# protol.net
KiCad netlist of a schematic drawn in EAGLE
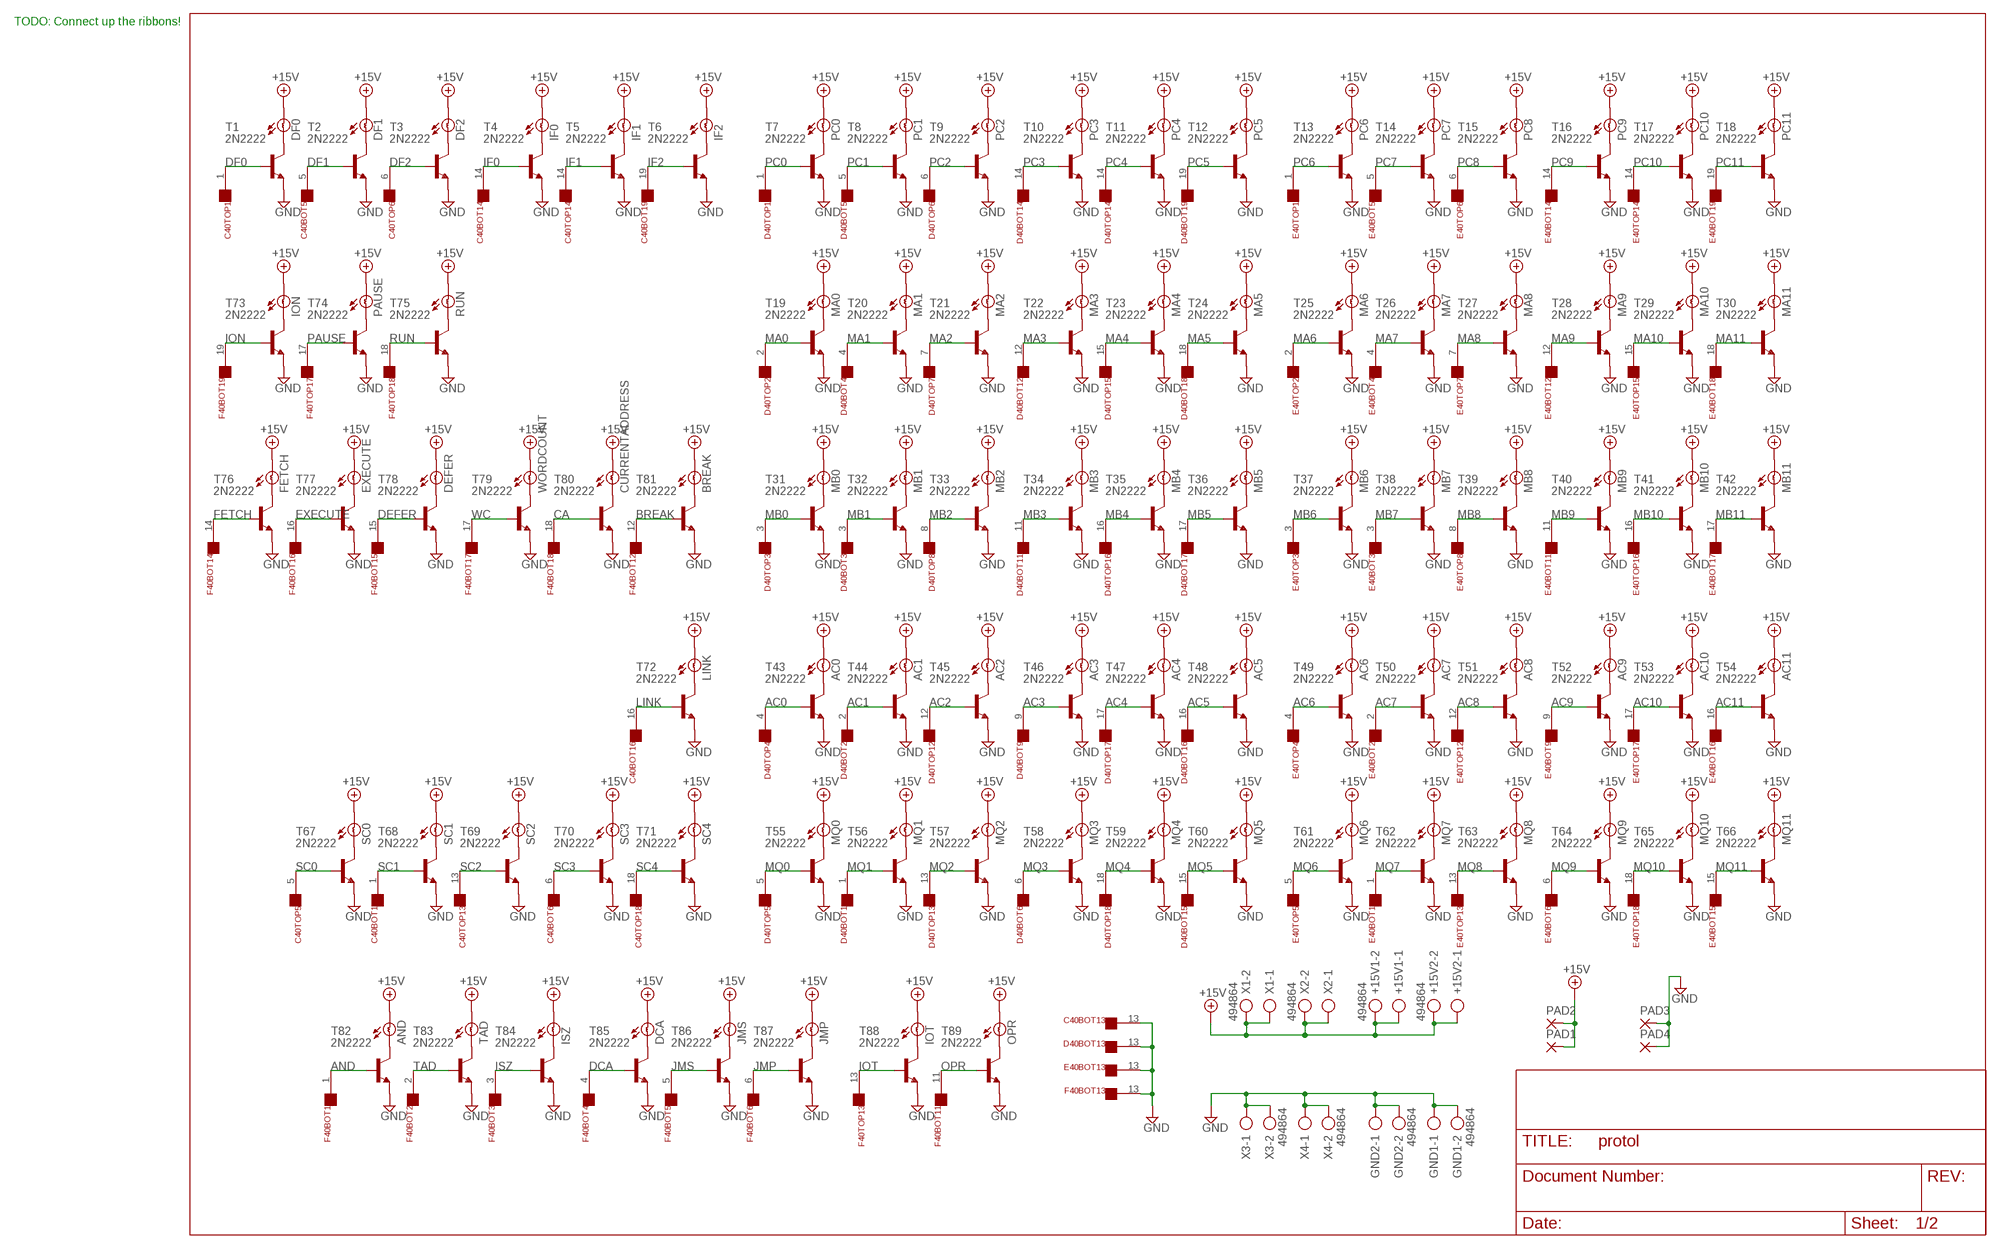
[diagram p0: schematic, sheet 1]
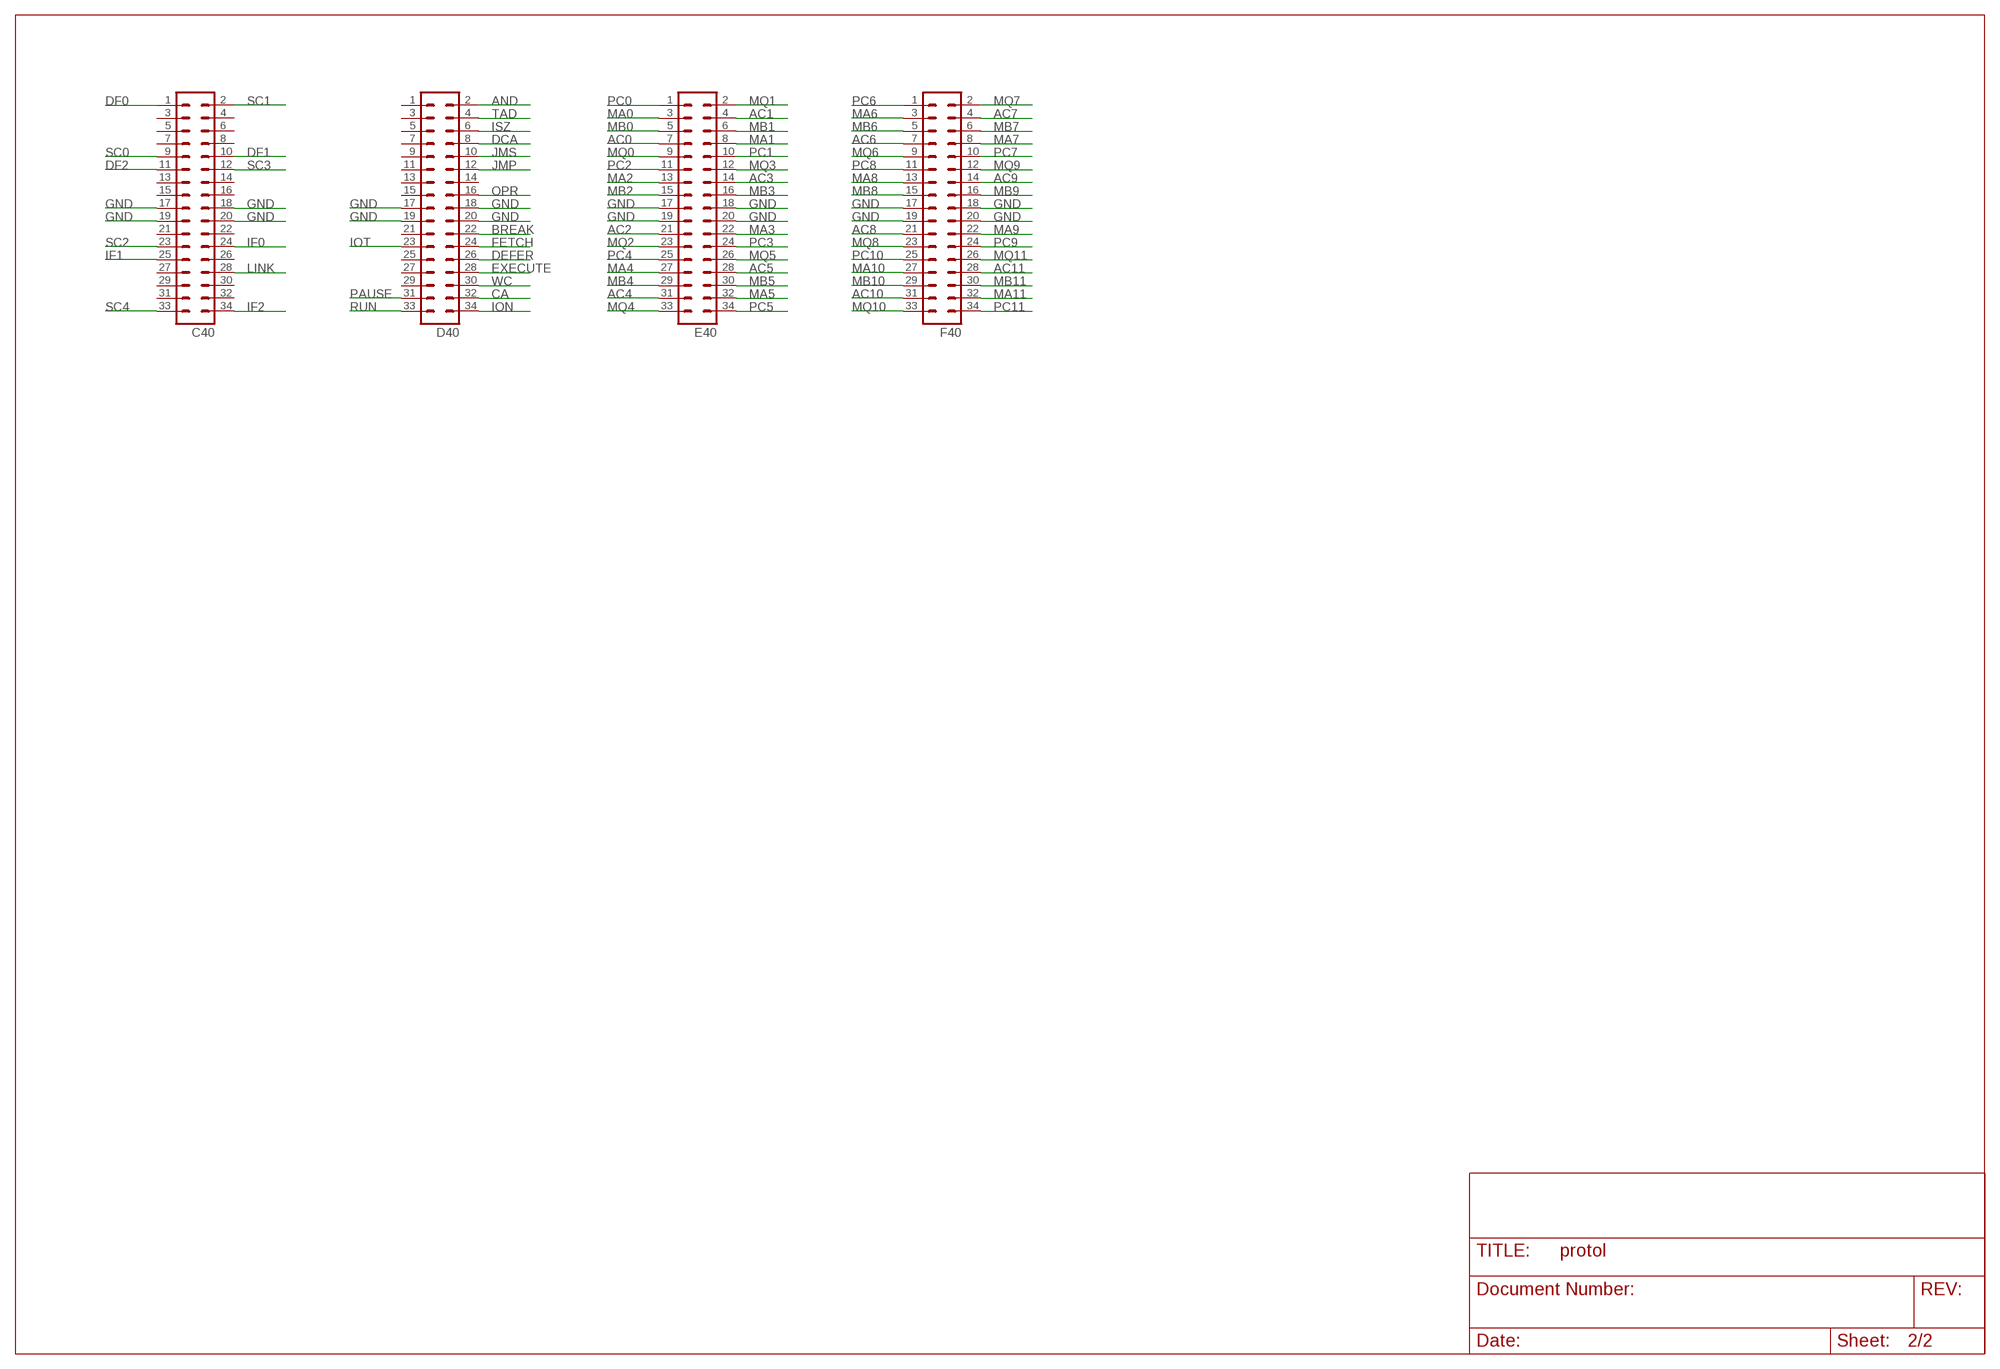
[diagram p1: schematic, sheet 2]

(export (version "E")
  (design (tool "Eeschema 10.0.6"))
  (components
    (comp (ref "C40")
      (value "MA17-2")
      (footprint "eagle-import:MA17-2")
      (libsource (lib "eagle-import") (part "MA17-2"))
    )
    (comp (ref "D40")
      (value "MA17-2")
      (footprint "eagle-import:MA17-2")
      (libsource (lib "eagle-import") (part "MA17-2"))
    )
    (comp (ref "E40")
      (value "MA17-2")
      (footprint "eagle-import:MA17-2")
      (libsource (lib "eagle-import") (part "MA17-2"))
    )
    (comp (ref "F40")
      (value "MA17-2")
      (footprint "eagle-import:MA17-2")
      (libsource (lib "eagle-import") (part "MA17-2"))
    )
    (comp (ref "+15V1")
      (value "494864")
      (footprint "eagle-import:AK500_2")
      (libsource (lib "eagle-import") (part "AK500/2"))
    )
    (comp (ref "+15V2")
      (value "494864")
      (footprint "eagle-import:AK500_2")
      (libsource (lib "eagle-import") (part "AK500/2"))
    )
    (comp (ref "AC0")
      (value "BULB")
      (footprint "eagle-import:BULB")
      (libsource (lib "eagle-import") (part "BULB"))
    )
    (comp (ref "AC1")
      (value "BULB")
      (footprint "eagle-import:BULB")
      (libsource (lib "eagle-import") (part "BULB"))
    )
    (comp (ref "AC2")
      (value "BULB")
      (footprint "eagle-import:BULB")
      (libsource (lib "eagle-import") (part "BULB"))
    )
    (comp (ref "AC3")
      (value "BULB")
      (footprint "eagle-import:BULB")
      (libsource (lib "eagle-import") (part "BULB"))
    )
    (comp (ref "AC4")
      (value "BULB")
      (footprint "eagle-import:BULB")
      (libsource (lib "eagle-import") (part "BULB"))
    )
    (comp (ref "AC5")
      (value "BULB")
      (footprint "eagle-import:BULB")
      (libsource (lib "eagle-import") (part "BULB"))
    )
    (comp (ref "AC6")
      (value "BULB")
      (footprint "eagle-import:BULB")
      (libsource (lib "eagle-import") (part "BULB"))
    )
    (comp (ref "AC7")
      (value "BULB")
      (footprint "eagle-import:BULB")
      (libsource (lib "eagle-import") (part "BULB"))
    )
    (comp (ref "AC8")
      (value "BULB")
      (footprint "eagle-import:BULB")
      (libsource (lib "eagle-import") (part "BULB"))
    )
    (comp (ref "AC9")
      (value "BULB")
      (footprint "eagle-import:BULB")
      (libsource (lib "eagle-import") (part "BULB"))
    )
    (comp (ref "AC10")
      (value "BULB")
      (footprint "eagle-import:BULB")
      (libsource (lib "eagle-import") (part "BULB"))
    )
    (comp (ref "AC11")
      (value "BULB")
      (footprint "eagle-import:BULB")
      (libsource (lib "eagle-import") (part "BULB"))
    )
    (comp (ref "AND")
      (value "BULB")
      (footprint "eagle-import:BULB")
      (libsource (lib "eagle-import") (part "BULB"))
    )
    (comp (ref "BREAK")
      (value "BULB")
      (footprint "eagle-import:BULB")
      (libsource (lib "eagle-import") (part "BULB"))
    )
    (comp (ref "C40BOT")
      (value "FLEX19")
      (footprint "eagle-import:FLEX19")
      (libsource (lib "eagle-import") (part "FLEX19"))
    )
    (comp (ref "C40TOP")
      (value "FLEX19")
      (footprint "eagle-import:FLEX19")
      (libsource (lib "eagle-import") (part "FLEX19"))
    )
    (comp (ref "CURRENTADDRESS")
      (value "BULB")
      (footprint "eagle-import:BULB")
      (libsource (lib "eagle-import") (part "BULB"))
    )
    (comp (ref "D40BOT")
      (value "FLEX19")
      (footprint "eagle-import:FLEX19")
      (libsource (lib "eagle-import") (part "FLEX19"))
    )
    (comp (ref "D40TOP")
      (value "FLEX19")
      (footprint "eagle-import:FLEX19")
      (libsource (lib "eagle-import") (part "FLEX19"))
    )
    (comp (ref "DCA")
      (value "BULB")
      (footprint "eagle-import:BULB")
      (libsource (lib "eagle-import") (part "BULB"))
    )
    (comp (ref "DEFER")
      (value "BULB")
      (footprint "eagle-import:BULB")
      (libsource (lib "eagle-import") (part "BULB"))
    )
    (comp (ref "DF0")
      (value "BULB")
      (footprint "eagle-import:BULB")
      (libsource (lib "eagle-import") (part "BULB"))
    )
    (comp (ref "DF1")
      (value "BULB")
      (footprint "eagle-import:BULB")
      (libsource (lib "eagle-import") (part "BULB"))
    )
    (comp (ref "DF2")
      (value "BULB")
      (footprint "eagle-import:BULB")
      (libsource (lib "eagle-import") (part "BULB"))
    )
    (comp (ref "E40BOT")
      (value "FLEX19")
      (footprint "eagle-import:FLEX19")
      (libsource (lib "eagle-import") (part "FLEX19"))
    )
    (comp (ref "E40TOP")
      (value "FLEX19")
      (footprint "eagle-import:FLEX19")
      (libsource (lib "eagle-import") (part "FLEX19"))
    )
    (comp (ref "EXECUTE")
      (value "BULB")
      (footprint "eagle-import:BULB")
      (libsource (lib "eagle-import") (part "BULB"))
    )
    (comp (ref "F40BOT")
      (value "FLEX19")
      (footprint "eagle-import:FLEX19")
      (libsource (lib "eagle-import") (part "FLEX19"))
    )
    (comp (ref "F40TOP")
      (value "FLEX19")
      (footprint "eagle-import:FLEX19")
      (libsource (lib "eagle-import") (part "FLEX19"))
    )
    (comp (ref "FETCH")
      (value "BULB")
      (footprint "eagle-import:BULB")
      (libsource (lib "eagle-import") (part "BULB"))
    )
    (comp (ref "GND1")
      (value "494864")
      (footprint "eagle-import:AK500_2")
      (libsource (lib "eagle-import") (part "AK500/2"))
    )
    (comp (ref "GND2")
      (value "494864")
      (footprint "eagle-import:AK500_2")
      (libsource (lib "eagle-import") (part "AK500/2"))
    )
    (comp (ref "IF0")
      (value "BULB")
      (footprint "eagle-import:BULB")
      (libsource (lib "eagle-import") (part "BULB"))
    )
    (comp (ref "IF1")
      (value "BULB")
      (footprint "eagle-import:BULB")
      (libsource (lib "eagle-import") (part "BULB"))
    )
    (comp (ref "IF2")
      (value "BULB")
      (footprint "eagle-import:BULB")
      (libsource (lib "eagle-import") (part "BULB"))
    )
    (comp (ref "ION")
      (value "BULB")
      (footprint "eagle-import:BULB")
      (libsource (lib "eagle-import") (part "BULB"))
    )
    (comp (ref "IOT")
      (value "BULB")
      (footprint "eagle-import:BULB")
      (libsource (lib "eagle-import") (part "BULB"))
    )
    (comp (ref "ISZ")
      (value "BULB")
      (footprint "eagle-import:BULB")
      (libsource (lib "eagle-import") (part "BULB"))
    )
    (comp (ref "JMP")
      (value "BULB")
      (footprint "eagle-import:BULB")
      (libsource (lib "eagle-import") (part "BULB"))
    )
    (comp (ref "JMS")
      (value "BULB")
      (footprint "eagle-import:BULB")
      (libsource (lib "eagle-import") (part "BULB"))
    )
    (comp (ref "LINK")
      (value "BULB")
      (footprint "eagle-import:BULB")
      (libsource (lib "eagle-import") (part "BULB"))
    )
    (comp (ref "MA0")
      (value "BULB")
      (footprint "eagle-import:BULB")
      (libsource (lib "eagle-import") (part "BULB"))
    )
    (comp (ref "MA1")
      (value "BULB")
      (footprint "eagle-import:BULB")
      (libsource (lib "eagle-import") (part "BULB"))
    )
    (comp (ref "MA2")
      (value "BULB")
      (footprint "eagle-import:BULB")
      (libsource (lib "eagle-import") (part "BULB"))
    )
    (comp (ref "MA3")
      (value "BULB")
      (footprint "eagle-import:BULB")
      (libsource (lib "eagle-import") (part "BULB"))
    )
    (comp (ref "MA4")
      (value "BULB")
      (footprint "eagle-import:BULB")
      (libsource (lib "eagle-import") (part "BULB"))
    )
    (comp (ref "MA5")
      (value "BULB")
      (footprint "eagle-import:BULB")
      (libsource (lib "eagle-import") (part "BULB"))
    )
    (comp (ref "MA6")
      (value "BULB")
      (footprint "eagle-import:BULB")
      (libsource (lib "eagle-import") (part "BULB"))
    )
    (comp (ref "MA7")
      (value "BULB")
      (footprint "eagle-import:BULB")
      (libsource (lib "eagle-import") (part "BULB"))
    )
    (comp (ref "MA8")
      (value "BULB")
      (footprint "eagle-import:BULB")
      (libsource (lib "eagle-import") (part "BULB"))
    )
    (comp (ref "MA9")
      (value "BULB")
      (footprint "eagle-import:BULB")
      (libsource (lib "eagle-import") (part "BULB"))
    )
    (comp (ref "MA10")
      (value "BULB")
      (footprint "eagle-import:BULB")
      (libsource (lib "eagle-import") (part "BULB"))
    )
    (comp (ref "MA11")
      (value "BULB")
      (footprint "eagle-import:BULB")
      (libsource (lib "eagle-import") (part "BULB"))
    )
    (comp (ref "MB0")
      (value "BULB")
      (footprint "eagle-import:BULB")
      (libsource (lib "eagle-import") (part "BULB"))
    )
    (comp (ref "MB1")
      (value "BULB")
      (footprint "eagle-import:BULB")
      (libsource (lib "eagle-import") (part "BULB"))
    )
    (comp (ref "MB2")
      (value "BULB")
      (footprint "eagle-import:BULB")
      (libsource (lib "eagle-import") (part "BULB"))
    )
    (comp (ref "MB3")
      (value "BULB")
      (footprint "eagle-import:BULB")
      (libsource (lib "eagle-import") (part "BULB"))
    )
    (comp (ref "MB4")
      (value "BULB")
      (footprint "eagle-import:BULB")
      (libsource (lib "eagle-import") (part "BULB"))
    )
    (comp (ref "MB5")
      (value "BULB")
      (footprint "eagle-import:BULB")
      (libsource (lib "eagle-import") (part "BULB"))
    )
    (comp (ref "MB6")
      (value "BULB")
      (footprint "eagle-import:BULB")
      (libsource (lib "eagle-import") (part "BULB"))
    )
    (comp (ref "MB7")
      (value "BULB")
      (footprint "eagle-import:BULB")
      (libsource (lib "eagle-import") (part "BULB"))
    )
    (comp (ref "MB8")
      (value "BULB")
      (footprint "eagle-import:BULB")
      (libsource (lib "eagle-import") (part "BULB"))
    )
    (comp (ref "MB9")
      (value "BULB")
      (footprint "eagle-import:BULB")
      (libsource (lib "eagle-import") (part "BULB"))
    )
    (comp (ref "MB10")
      (value "BULB")
      (footprint "eagle-import:BULB")
      (libsource (lib "eagle-import") (part "BULB"))
    )
    (comp (ref "MB11")
      (value "BULB")
      (footprint "eagle-import:BULB")
      (libsource (lib "eagle-import") (part "BULB"))
    )
    (comp (ref "MQ0")
      (value "BULB")
      (footprint "eagle-import:BULB")
      (libsource (lib "eagle-import") (part "BULB"))
    )
    (comp (ref "MQ1")
      (value "BULB")
      (footprint "eagle-import:BULB")
      (libsource (lib "eagle-import") (part "BULB"))
    )
    (comp (ref "MQ2")
      (value "BULB")
      (footprint "eagle-import:BULB")
      (libsource (lib "eagle-import") (part "BULB"))
    )
    (comp (ref "MQ3")
      (value "BULB")
      (footprint "eagle-import:BULB")
      (libsource (lib "eagle-import") (part "BULB"))
    )
    (comp (ref "MQ4")
      (value "BULB")
      (footprint "eagle-import:BULB")
      (libsource (lib "eagle-import") (part "BULB"))
    )
    (comp (ref "MQ5")
      (value "BULB")
      (footprint "eagle-import:BULB")
      (libsource (lib "eagle-import") (part "BULB"))
    )
    (comp (ref "MQ6")
      (value "BULB")
      (footprint "eagle-import:BULB")
      (libsource (lib "eagle-import") (part "BULB"))
    )
    (comp (ref "MQ7")
      (value "BULB")
      (footprint "eagle-import:BULB")
      (libsource (lib "eagle-import") (part "BULB"))
    )
    (comp (ref "MQ8")
      (value "BULB")
      (footprint "eagle-import:BULB")
      (libsource (lib "eagle-import") (part "BULB"))
    )
    (comp (ref "MQ9")
      (value "BULB")
      (footprint "eagle-import:BULB")
      (libsource (lib "eagle-import") (part "BULB"))
    )
    (comp (ref "MQ10")
      (value "BULB")
      (footprint "eagle-import:BULB")
      (libsource (lib "eagle-import") (part "BULB"))
    )
    (comp (ref "MQ11")
      (value "BULB")
      (footprint "eagle-import:BULB")
      (libsource (lib "eagle-import") (part "BULB"))
    )
    (comp (ref "OPR")
      (value "BULB")
      (footprint "eagle-import:BULB")
      (libsource (lib "eagle-import") (part "BULB"))
    )
    (comp (ref "PAD1")
      (value "2,54/0,8")
      (footprint "eagle-import:2,54_0,8")
      (libsource (lib "eagle-import") (part "2,54/0,8"))
    )
    (comp (ref "PAD2")
      (value "2,54/0,8")
      (footprint "eagle-import:2,54_0,8")
      (libsource (lib "eagle-import") (part "2,54/0,8"))
    )
    (comp (ref "PAD3")
      (value "2,54/0,8")
      (footprint "eagle-import:2,54_0,8")
      (libsource (lib "eagle-import") (part "2,54/0,8"))
    )
    (comp (ref "PAD4")
      (value "2,54/0,8")
      (footprint "eagle-import:2,54_0,8")
      (libsource (lib "eagle-import") (part "2,54/0,8"))
    )
    (comp (ref "PAUSE")
      (value "BULB")
      (footprint "eagle-import:BULB")
      (libsource (lib "eagle-import") (part "BULB"))
    )
    (comp (ref "PC0")
      (value "BULB")
      (footprint "eagle-import:BULB")
      (libsource (lib "eagle-import") (part "BULB"))
    )
    (comp (ref "PC1")
      (value "BULB")
      (footprint "eagle-import:BULB")
      (libsource (lib "eagle-import") (part "BULB"))
    )
    (comp (ref "PC2")
      (value "BULB")
      (footprint "eagle-import:BULB")
      (libsource (lib "eagle-import") (part "BULB"))
    )
    (comp (ref "PC3")
      (value "BULB")
      (footprint "eagle-import:BULB")
      (libsource (lib "eagle-import") (part "BULB"))
    )
    (comp (ref "PC4")
      (value "BULB")
      (footprint "eagle-import:BULB")
      (libsource (lib "eagle-import") (part "BULB"))
    )
    (comp (ref "PC5")
      (value "BULB")
      (footprint "eagle-import:BULB")
      (libsource (lib "eagle-import") (part "BULB"))
    )
    (comp (ref "PC6")
      (value "BULB")
      (footprint "eagle-import:BULB")
      (libsource (lib "eagle-import") (part "BULB"))
    )
    (comp (ref "PC7")
      (value "BULB")
      (footprint "eagle-import:BULB")
      (libsource (lib "eagle-import") (part "BULB"))
    )
    (comp (ref "PC8")
      (value "BULB")
      (footprint "eagle-import:BULB")
      (libsource (lib "eagle-import") (part "BULB"))
    )
    (comp (ref "PC9")
      (value "BULB")
      (footprint "eagle-import:BULB")
      (libsource (lib "eagle-import") (part "BULB"))
    )
    (comp (ref "PC10")
      (value "BULB")
      (footprint "eagle-import:BULB")
      (libsource (lib "eagle-import") (part "BULB"))
    )
    (comp (ref "PC11")
      (value "BULB")
      (footprint "eagle-import:BULB")
      (libsource (lib "eagle-import") (part "BULB"))
    )
    (comp (ref "RUN")
      (value "BULB")
      (footprint "eagle-import:BULB")
      (libsource (lib "eagle-import") (part "BULB"))
    )
    (comp (ref "SC0")
      (value "BULB")
      (footprint "eagle-import:BULB")
      (libsource (lib "eagle-import") (part "BULB"))
    )
    (comp (ref "SC1")
      (value "BULB")
      (footprint "eagle-import:BULB")
      (libsource (lib "eagle-import") (part "BULB"))
    )
    (comp (ref "SC2")
      (value "BULB")
      (footprint "eagle-import:BULB")
      (libsource (lib "eagle-import") (part "BULB"))
    )
    (comp (ref "SC3")
      (value "BULB")
      (footprint "eagle-import:BULB")
      (libsource (lib "eagle-import") (part "BULB"))
    )
    (comp (ref "SC4")
      (value "BULB")
      (footprint "eagle-import:BULB")
      (libsource (lib "eagle-import") (part "BULB"))
    )
    (comp (ref "T1")
      (value "2N2222")
      (footprint "eagle-import:TO92")
      (libsource (lib "eagle-import") (part "-NPN-TO92"))
    )
    (comp (ref "T2")
      (value "2N2222")
      (footprint "eagle-import:TO92")
      (libsource (lib "eagle-import") (part "-NPN-TO92"))
    )
    (comp (ref "T3")
      (value "2N2222")
      (footprint "eagle-import:TO92")
      (libsource (lib "eagle-import") (part "-NPN-TO92"))
    )
    (comp (ref "T4")
      (value "2N2222")
      (footprint "eagle-import:TO92")
      (libsource (lib "eagle-import") (part "-NPN-TO92"))
    )
    (comp (ref "T5")
      (value "2N2222")
      (footprint "eagle-import:TO92")
      (libsource (lib "eagle-import") (part "-NPN-TO92"))
    )
    (comp (ref "T6")
      (value "2N2222")
      (footprint "eagle-import:TO92")
      (libsource (lib "eagle-import") (part "-NPN-TO92"))
    )
    (comp (ref "T7")
      (value "2N2222")
      (footprint "eagle-import:TO92")
      (libsource (lib "eagle-import") (part "-NPN-TO92"))
    )
    (comp (ref "T8")
      (value "2N2222")
      (footprint "eagle-import:TO92")
      (libsource (lib "eagle-import") (part "-NPN-TO92"))
    )
    (comp (ref "T9")
      (value "2N2222")
      (footprint "eagle-import:TO92")
      (libsource (lib "eagle-import") (part "-NPN-TO92"))
    )
    (comp (ref "T10")
      (value "2N2222")
      (footprint "eagle-import:TO92")
      (libsource (lib "eagle-import") (part "-NPN-TO92"))
    )
    (comp (ref "T11")
      (value "2N2222")
      (footprint "eagle-import:TO92")
      (libsource (lib "eagle-import") (part "-NPN-TO92"))
    )
    (comp (ref "T12")
      (value "2N2222")
      (footprint "eagle-import:TO92")
      (libsource (lib "eagle-import") (part "-NPN-TO92"))
    )
    (comp (ref "T13")
      (value "2N2222")
      (footprint "eagle-import:TO92")
      (libsource (lib "eagle-import") (part "-NPN-TO92"))
    )
    (comp (ref "T14")
      (value "2N2222")
      (footprint "eagle-import:TO92")
      (libsource (lib "eagle-import") (part "-NPN-TO92"))
    )
    (comp (ref "T15")
      (value "2N2222")
      (footprint "eagle-import:TO92")
      (libsource (lib "eagle-import") (part "-NPN-TO92"))
    )
    (comp (ref "T16")
      (value "2N2222")
      (footprint "eagle-import:TO92")
      (libsource (lib "eagle-import") (part "-NPN-TO92"))
    )
    (comp (ref "T17")
      (value "2N2222")
      (footprint "eagle-import:TO92")
      (libsource (lib "eagle-import") (part "-NPN-TO92"))
    )
    (comp (ref "T18")
      (value "2N2222")
      (footprint "eagle-import:TO92")
      (libsource (lib "eagle-import") (part "-NPN-TO92"))
    )
    (comp (ref "T19")
      (value "2N2222")
      (footprint "eagle-import:TO92")
      (libsource (lib "eagle-import") (part "-NPN-TO92"))
    )
    (comp (ref "T20")
      (value "2N2222")
      (footprint "eagle-import:TO92")
      (libsource (lib "eagle-import") (part "-NPN-TO92"))
    )
    (comp (ref "T21")
      (value "2N2222")
      (footprint "eagle-import:TO92")
      (libsource (lib "eagle-import") (part "-NPN-TO92"))
    )
    (comp (ref "T22")
      (value "2N2222")
      (footprint "eagle-import:TO92")
      (libsource (lib "eagle-import") (part "-NPN-TO92"))
    )
    (comp (ref "T23")
      (value "2N2222")
      (footprint "eagle-import:TO92")
      (libsource (lib "eagle-import") (part "-NPN-TO92"))
    )
    (comp (ref "T24")
      (value "2N2222")
      (footprint "eagle-import:TO92")
      (libsource (lib "eagle-import") (part "-NPN-TO92"))
    )
    (comp (ref "T25")
      (value "2N2222")
      (footprint "eagle-import:TO92")
      (libsource (lib "eagle-import") (part "-NPN-TO92"))
    )
    (comp (ref "T26")
      (value "2N2222")
      (footprint "eagle-import:TO92")
      (libsource (lib "eagle-import") (part "-NPN-TO92"))
    )
    (comp (ref "T27")
      (value "2N2222")
      (footprint "eagle-import:TO92")
      (libsource (lib "eagle-import") (part "-NPN-TO92"))
    )
    (comp (ref "T28")
      (value "2N2222")
      (footprint "eagle-import:TO92")
      (libsource (lib "eagle-import") (part "-NPN-TO92"))
    )
    (comp (ref "T29")
      (value "2N2222")
      (footprint "eagle-import:TO92")
      (libsource (lib "eagle-import") (part "-NPN-TO92"))
    )
    (comp (ref "T30")
      (value "2N2222")
      (footprint "eagle-import:TO92")
      (libsource (lib "eagle-import") (part "-NPN-TO92"))
    )
    (comp (ref "T31")
      (value "2N2222")
      (footprint "eagle-import:TO92")
      (libsource (lib "eagle-import") (part "-NPN-TO92"))
    )
    (comp (ref "T32")
      (value "2N2222")
      (footprint "eagle-import:TO92")
      (libsource (lib "eagle-import") (part "-NPN-TO92"))
    )
    (comp (ref "T33")
      (value "2N2222")
      (footprint "eagle-import:TO92")
      (libsource (lib "eagle-import") (part "-NPN-TO92"))
    )
    (comp (ref "T34")
      (value "2N2222")
      (footprint "eagle-import:TO92")
      (libsource (lib "eagle-import") (part "-NPN-TO92"))
    )
    (comp (ref "T35")
      (value "2N2222")
      (footprint "eagle-import:TO92")
      (libsource (lib "eagle-import") (part "-NPN-TO92"))
    )
    (comp (ref "T36")
      (value "2N2222")
      (footprint "eagle-import:TO92")
      (libsource (lib "eagle-import") (part "-NPN-TO92"))
    )
    (comp (ref "T37")
      (value "2N2222")
      (footprint "eagle-import:TO92")
      (libsource (lib "eagle-import") (part "-NPN-TO92"))
    )
    (comp (ref "T38")
      (value "2N2222")
      (footprint "eagle-import:TO92")
      (libsource (lib "eagle-import") (part "-NPN-TO92"))
    )
    (comp (ref "T39")
      (value "2N2222")
      (footprint "eagle-import:TO92")
      (libsource (lib "eagle-import") (part "-NPN-TO92"))
    )
    (comp (ref "T40")
      (value "2N2222")
      (footprint "eagle-import:TO92")
      (libsource (lib "eagle-import") (part "-NPN-TO92"))
    )
    (comp (ref "T41")
      (value "2N2222")
      (footprint "eagle-import:TO92")
      (libsource (lib "eagle-import") (part "-NPN-TO92"))
    )
    (comp (ref "T42")
      (value "2N2222")
      (footprint "eagle-import:TO92")
      (libsource (lib "eagle-import") (part "-NPN-TO92"))
    )
    (comp (ref "T43")
      (value "2N2222")
      (footprint "eagle-import:TO92")
      (libsource (lib "eagle-import") (part "-NPN-TO92"))
    )
    (comp (ref "T44")
      (value "2N2222")
      (footprint "eagle-import:TO92")
      (libsource (lib "eagle-import") (part "-NPN-TO92"))
    )
    (comp (ref "T45")
      (value "2N2222")
      (footprint "eagle-import:TO92")
      (libsource (lib "eagle-import") (part "-NPN-TO92"))
    )
    (comp (ref "T46")
      (value "2N2222")
      (footprint "eagle-import:TO92")
      (libsource (lib "eagle-import") (part "-NPN-TO92"))
    )
    (comp (ref "T47")
      (value "2N2222")
      (footprint "eagle-import:TO92")
      (libsource (lib "eagle-import") (part "-NPN-TO92"))
    )
    (comp (ref "T48")
      (value "2N2222")
      (footprint "eagle-import:TO92")
      (libsource (lib "eagle-import") (part "-NPN-TO92"))
    )
    (comp (ref "T49")
      (value "2N2222")
      (footprint "eagle-import:TO92")
      (libsource (lib "eagle-import") (part "-NPN-TO92"))
    )
    (comp (ref "T50")
      (value "2N2222")
      (footprint "eagle-import:TO92")
      (libsource (lib "eagle-import") (part "-NPN-TO92"))
    )
    (comp (ref "T51")
      (value "2N2222")
      (footprint "eagle-import:TO92")
      (libsource (lib "eagle-import") (part "-NPN-TO92"))
    )
    (comp (ref "T52")
      (value "2N2222")
      (footprint "eagle-import:TO92")
      (libsource (lib "eagle-import") (part "-NPN-TO92"))
    )
    (comp (ref "T53")
      (value "2N2222")
      (footprint "eagle-import:TO92")
      (libsource (lib "eagle-import") (part "-NPN-TO92"))
    )
    (comp (ref "T54")
      (value "2N2222")
      (footprint "eagle-import:TO92")
      (libsource (lib "eagle-import") (part "-NPN-TO92"))
    )
    (comp (ref "T55")
      (value "2N2222")
      (footprint "eagle-import:TO92")
      (libsource (lib "eagle-import") (part "-NPN-TO92"))
    )
    (comp (ref "T56")
      (value "2N2222")
      (footprint "eagle-import:TO92")
      (libsource (lib "eagle-import") (part "-NPN-TO92"))
    )
    (comp (ref "T57")
      (value "2N2222")
      (footprint "eagle-import:TO92")
      (libsource (lib "eagle-import") (part "-NPN-TO92"))
    )
    (comp (ref "T58")
      (value "2N2222")
      (footprint "eagle-import:TO92")
      (libsource (lib "eagle-import") (part "-NPN-TO92"))
    )
    (comp (ref "T59")
      (value "2N2222")
      (footprint "eagle-import:TO92")
      (libsource (lib "eagle-import") (part "-NPN-TO92"))
    )
    (comp (ref "T60")
      (value "2N2222")
      (footprint "eagle-import:TO92")
      (libsource (lib "eagle-import") (part "-NPN-TO92"))
    )
    (comp (ref "T61")
      (value "2N2222")
      (footprint "eagle-import:TO92")
      (libsource (lib "eagle-import") (part "-NPN-TO92"))
    )
    (comp (ref "T62")
      (value "2N2222")
      (footprint "eagle-import:TO92")
      (libsource (lib "eagle-import") (part "-NPN-TO92"))
    )
    (comp (ref "T63")
      (value "2N2222")
      (footprint "eagle-import:TO92")
      (libsource (lib "eagle-import") (part "-NPN-TO92"))
    )
    (comp (ref "T64")
      (value "2N2222")
      (footprint "eagle-import:TO92")
      (libsource (lib "eagle-import") (part "-NPN-TO92"))
    )
    (comp (ref "T65")
      (value "2N2222")
      (footprint "eagle-import:TO92")
      (libsource (lib "eagle-import") (part "-NPN-TO92"))
    )
    (comp (ref "T66")
      (value "2N2222")
      (footprint "eagle-import:TO92")
      (libsource (lib "eagle-import") (part "-NPN-TO92"))
    )
    (comp (ref "T67")
      (value "2N2222")
      (footprint "eagle-import:TO92")
      (libsource (lib "eagle-import") (part "-NPN-TO92"))
    )
    (comp (ref "T68")
      (value "2N2222")
      (footprint "eagle-import:TO92")
      (libsource (lib "eagle-import") (part "-NPN-TO92"))
    )
    (comp (ref "T69")
      (value "2N2222")
      (footprint "eagle-import:TO92")
      (libsource (lib "eagle-import") (part "-NPN-TO92"))
    )
    (comp (ref "T70")
      (value "2N2222")
      (footprint "eagle-import:TO92")
      (libsource (lib "eagle-import") (part "-NPN-TO92"))
    )
    (comp (ref "T71")
      (value "2N2222")
      (footprint "eagle-import:TO92")
      (libsource (lib "eagle-import") (part "-NPN-TO92"))
    )
    (comp (ref "T72")
      (value "2N2222")
      (footprint "eagle-import:TO92")
      (libsource (lib "eagle-import") (part "-NPN-TO92"))
    )
    (comp (ref "T73")
      (value "2N2222")
      (footprint "eagle-import:TO92")
      (libsource (lib "eagle-import") (part "-NPN-TO92"))
    )
    (comp (ref "T74")
      (value "2N2222")
      (footprint "eagle-import:TO92")
      (libsource (lib "eagle-import") (part "-NPN-TO92"))
    )
    (comp (ref "T75")
      (value "2N2222")
      (footprint "eagle-import:TO92")
      (libsource (lib "eagle-import") (part "-NPN-TO92"))
    )
    (comp (ref "T76")
      (value "2N2222")
      (footprint "eagle-import:TO92")
      (libsource (lib "eagle-import") (part "-NPN-TO92"))
    )
    (comp (ref "T77")
      (value "2N2222")
      (footprint "eagle-import:TO92")
      (libsource (lib "eagle-import") (part "-NPN-TO92"))
    )
    (comp (ref "T78")
      (value "2N2222")
      (footprint "eagle-import:TO92")
      (libsource (lib "eagle-import") (part "-NPN-TO92"))
    )
    (comp (ref "T79")
      (value "2N2222")
      (footprint "eagle-import:TO92")
      (libsource (lib "eagle-import") (part "-NPN-TO92"))
    )
    (comp (ref "T80")
      (value "2N2222")
      (footprint "eagle-import:TO92")
      (libsource (lib "eagle-import") (part "-NPN-TO92"))
    )
    (comp (ref "T81")
      (value "2N2222")
      (footprint "eagle-import:TO92")
      (libsource (lib "eagle-import") (part "-NPN-TO92"))
    )
    (comp (ref "T82")
      (value "2N2222")
      (footprint "eagle-import:TO92")
      (libsource (lib "eagle-import") (part "-NPN-TO92"))
    )
    (comp (ref "T83")
      (value "2N2222")
      (footprint "eagle-import:TO92")
      (libsource (lib "eagle-import") (part "-NPN-TO92"))
    )
    (comp (ref "T84")
      (value "2N2222")
      (footprint "eagle-import:TO92")
      (libsource (lib "eagle-import") (part "-NPN-TO92"))
    )
    (comp (ref "T85")
      (value "2N2222")
      (footprint "eagle-import:TO92")
      (libsource (lib "eagle-import") (part "-NPN-TO92"))
    )
    (comp (ref "T86")
      (value "2N2222")
      (footprint "eagle-import:TO92")
      (libsource (lib "eagle-import") (part "-NPN-TO92"))
    )
    (comp (ref "T87")
      (value "2N2222")
      (footprint "eagle-import:TO92")
      (libsource (lib "eagle-import") (part "-NPN-TO92"))
    )
    (comp (ref "T88")
      (value "2N2222")
      (footprint "eagle-import:TO92")
      (libsource (lib "eagle-import") (part "-NPN-TO92"))
    )
    (comp (ref "T89")
      (value "2N2222")
      (footprint "eagle-import:TO92")
      (libsource (lib "eagle-import") (part "-NPN-TO92"))
    )
    (comp (ref "TAD")
      (value "BULB")
      (footprint "eagle-import:BULB")
      (libsource (lib "eagle-import") (part "BULB"))
    )
    (comp (ref "WORDCOUNT")
      (value "BULB")
      (footprint "eagle-import:BULB")
      (libsource (lib "eagle-import") (part "BULB"))
    )
    (comp (ref "X1")
      (value "494864")
      (footprint "eagle-import:AK500_2")
      (libsource (lib "eagle-import") (part "AK500/2"))
    )
    (comp (ref "X2")
      (value "494864")
      (footprint "eagle-import:AK500_2")
      (libsource (lib "eagle-import") (part "AK500/2"))
    )
    (comp (ref "X3")
      (value "494864")
      (footprint "eagle-import:AK500_2")
      (libsource (lib "eagle-import") (part "AK500/2"))
    )
    (comp (ref "X4")
      (value "494864")
      (footprint "eagle-import:AK500_2")
      (libsource (lib "eagle-import") (part "AK500/2"))
    )
  )
  (nets
    (net (code "1") (name "+15V") (class "Default")
      (node (ref "+15V1") (pin "1") (pinfunction "KL_1") (pintype "passive"))
      (node (ref "+15V1") (pin "2") (pinfunction "KL_2") (pintype "passive"))
      (node (ref "+15V2") (pin "1") (pinfunction "KL_1") (pintype "passive"))
      (node (ref "+15V2") (pin "2") (pinfunction "KL_2") (pintype "passive"))
      (node (ref "AC0") (pin "A") (pinfunction "A_A") (pintype "passive"))
      (node (ref "AC1") (pin "A") (pinfunction "A_A") (pintype "passive"))
      (node (ref "AC10") (pin "A") (pinfunction "A_A") (pintype "passive"))
      (node (ref "AC11") (pin "A") (pinfunction "A_A") (pintype "passive"))
      (node (ref "AC2") (pin "A") (pinfunction "A_A") (pintype "passive"))
      (node (ref "AC3") (pin "A") (pinfunction "A_A") (pintype "passive"))
      (node (ref "AC4") (pin "A") (pinfunction "A_A") (pintype "passive"))
      (node (ref "AC5") (pin "A") (pinfunction "A_A") (pintype "passive"))
      (node (ref "AC6") (pin "A") (pinfunction "A_A") (pintype "passive"))
      (node (ref "AC7") (pin "A") (pinfunction "A_A") (pintype "passive"))
      (node (ref "AC8") (pin "A") (pinfunction "A_A") (pintype "passive"))
      (node (ref "AC9") (pin "A") (pinfunction "A_A") (pintype "passive"))
      (node (ref "AND") (pin "A") (pinfunction "A_A") (pintype "passive"))
      (node (ref "BREAK") (pin "A") (pinfunction "A_A") (pintype "passive"))
      (node (ref "CURRENTADDRESS") (pin "A") (pinfunction "A_A") (pintype "passive"))
      (node (ref "DCA") (pin "A") (pinfunction "A_A") (pintype "passive"))
      (node (ref "DEFER") (pin "A") (pinfunction "A_A") (pintype "passive"))
      (node (ref "DF0") (pin "A") (pinfunction "A_A") (pintype "passive"))
      (node (ref "DF1") (pin "A") (pinfunction "A_A") (pintype "passive"))
      (node (ref "DF2") (pin "A") (pinfunction "A_A") (pintype "passive"))
      (node (ref "EXECUTE") (pin "A") (pinfunction "A_A") (pintype "passive"))
      (node (ref "FETCH") (pin "A") (pinfunction "A_A") (pintype "passive"))
      (node (ref "IF0") (pin "A") (pinfunction "A_A") (pintype "passive"))
      (node (ref "IF1") (pin "A") (pinfunction "A_A") (pintype "passive"))
      (node (ref "IF2") (pin "A") (pinfunction "A_A") (pintype "passive"))
      (node (ref "ION") (pin "A") (pinfunction "A_A") (pintype "passive"))
      (node (ref "IOT") (pin "A") (pinfunction "A_A") (pintype "passive"))
      (node (ref "ISZ") (pin "A") (pinfunction "A_A") (pintype "passive"))
      (node (ref "JMP") (pin "A") (pinfunction "A_A") (pintype "passive"))
      (node (ref "JMS") (pin "A") (pinfunction "A_A") (pintype "passive"))
      (node (ref "LINK") (pin "A") (pinfunction "A_A") (pintype "passive"))
      (node (ref "MA0") (pin "A") (pinfunction "A_A") (pintype "passive"))
      (node (ref "MA1") (pin "A") (pinfunction "A_A") (pintype "passive"))
      (node (ref "MA10") (pin "A") (pinfunction "A_A") (pintype "passive"))
      (node (ref "MA11") (pin "A") (pinfunction "A_A") (pintype "passive"))
      (node (ref "MA2") (pin "A") (pinfunction "A_A") (pintype "passive"))
      (node (ref "MA3") (pin "A") (pinfunction "A_A") (pintype "passive"))
      (node (ref "MA4") (pin "A") (pinfunction "A_A") (pintype "passive"))
      (node (ref "MA5") (pin "A") (pinfunction "A_A") (pintype "passive"))
      (node (ref "MA6") (pin "A") (pinfunction "A_A") (pintype "passive"))
      (node (ref "MA7") (pin "A") (pinfunction "A_A") (pintype "passive"))
      (node (ref "MA8") (pin "A") (pinfunction "A_A") (pintype "passive"))
      (node (ref "MA9") (pin "A") (pinfunction "A_A") (pintype "passive"))
      (node (ref "MB0") (pin "A") (pinfunction "A_A") (pintype "passive"))
      (node (ref "MB1") (pin "A") (pinfunction "A_A") (pintype "passive"))
      (node (ref "MB10") (pin "A") (pinfunction "A_A") (pintype "passive"))
      (node (ref "MB11") (pin "A") (pinfunction "A_A") (pintype "passive"))
      (node (ref "MB2") (pin "A") (pinfunction "A_A") (pintype "passive"))
      (node (ref "MB3") (pin "A") (pinfunction "A_A") (pintype "passive"))
      (node (ref "MB4") (pin "A") (pinfunction "A_A") (pintype "passive"))
      (node (ref "MB5") (pin "A") (pinfunction "A_A") (pintype "passive"))
      (node (ref "MB6") (pin "A") (pinfunction "A_A") (pintype "passive"))
      (node (ref "MB7") (pin "A") (pinfunction "A_A") (pintype "passive"))
      (node (ref "MB8") (pin "A") (pinfunction "A_A") (pintype "passive"))
      (node (ref "MB9") (pin "A") (pinfunction "A_A") (pintype "passive"))
      (node (ref "MQ0") (pin "A") (pinfunction "A_A") (pintype "passive"))
      (node (ref "MQ1") (pin "A") (pinfunction "A_A") (pintype "passive"))
      (node (ref "MQ10") (pin "A") (pinfunction "A_A") (pintype "passive"))
      (node (ref "MQ11") (pin "A") (pinfunction "A_A") (pintype "passive"))
      (node (ref "MQ2") (pin "A") (pinfunction "A_A") (pintype "passive"))
      (node (ref "MQ3") (pin "A") (pinfunction "A_A") (pintype "passive"))
      (node (ref "MQ4") (pin "A") (pinfunction "A_A") (pintype "passive"))
      (node (ref "MQ5") (pin "A") (pinfunction "A_A") (pintype "passive"))
      (node (ref "MQ6") (pin "A") (pinfunction "A_A") (pintype "passive"))
      (node (ref "MQ7") (pin "A") (pinfunction "A_A") (pintype "passive"))
      (node (ref "MQ8") (pin "A") (pinfunction "A_A") (pintype "passive"))
      (node (ref "MQ9") (pin "A") (pinfunction "A_A") (pintype "passive"))
      (node (ref "OPR") (pin "A") (pinfunction "A_A") (pintype "passive"))
      (node (ref "PAD1") (pin "1") (pinfunction "P_1") (pintype "passive"))
      (node (ref "PAD2") (pin "1") (pinfunction "P_1") (pintype "passive"))
      (node (ref "PAUSE") (pin "A") (pinfunction "A_A") (pintype "passive"))
      (node (ref "PC0") (pin "A") (pinfunction "A_A") (pintype "passive"))
      (node (ref "PC1") (pin "A") (pinfunction "A_A") (pintype "passive"))
      (node (ref "PC10") (pin "A") (pinfunction "A_A") (pintype "passive"))
      (node (ref "PC11") (pin "A") (pinfunction "A_A") (pintype "passive"))
      (node (ref "PC2") (pin "A") (pinfunction "A_A") (pintype "passive"))
      (node (ref "PC3") (pin "A") (pinfunction "A_A") (pintype "passive"))
      (node (ref "PC4") (pin "A") (pinfunction "A_A") (pintype "passive"))
      (node (ref "PC5") (pin "A") (pinfunction "A_A") (pintype "passive"))
      (node (ref "PC6") (pin "A") (pinfunction "A_A") (pintype "passive"))
      (node (ref "PC7") (pin "A") (pinfunction "A_A") (pintype "passive"))
      (node (ref "PC8") (pin "A") (pinfunction "A_A") (pintype "passive"))
      (node (ref "PC9") (pin "A") (pinfunction "A_A") (pintype "passive"))
      (node (ref "RUN") (pin "A") (pinfunction "A_A") (pintype "passive"))
      (node (ref "SC0") (pin "A") (pinfunction "A_A") (pintype "passive"))
      (node (ref "SC1") (pin "A") (pinfunction "A_A") (pintype "passive"))
      (node (ref "SC2") (pin "A") (pinfunction "A_A") (pintype "passive"))
      (node (ref "SC3") (pin "A") (pinfunction "A_A") (pintype "passive"))
      (node (ref "SC4") (pin "A") (pinfunction "A_A") (pintype "passive"))
      (node (ref "TAD") (pin "A") (pinfunction "A_A") (pintype "passive"))
      (node (ref "WORDCOUNT") (pin "A") (pinfunction "A_A") (pintype "passive"))
      (node (ref "X1") (pin "1") (pinfunction "KL_1") (pintype "passive"))
      (node (ref "X1") (pin "2") (pinfunction "KL_2") (pintype "passive"))
      (node (ref "X2") (pin "1") (pinfunction "KL_1") (pintype "passive"))
      (node (ref "X2") (pin "2") (pinfunction "KL_2") (pintype "passive"))
    )
    (net (code "2") (name "AC0") (class "Default")
      (node (ref "D40TOP") (pin "4") (pinfunction "1_4") (pintype "passive"))
      (node (ref "E40") (pin "7") (pinfunction "7_7") (pintype "passive"))
      (node (ref "T43") (pin "2") (pinfunction "B_2") (pintype "passive"))
    )
    (net (code "3") (name "AC1") (class "Default")
      (node (ref "D40BOT") (pin "2") (pinfunction "1_2") (pintype "passive"))
      (node (ref "E40") (pin "4") (pinfunction "4_4") (pintype "passive"))
      (node (ref "T44") (pin "2") (pinfunction "B_2") (pintype "passive"))
    )
    (net (code "4") (name "AC2") (class "Default")
      (node (ref "D40TOP") (pin "12") (pinfunction "1_12") (pintype "passive"))
      (node (ref "E40") (pin "21") (pinfunction "21_21") (pintype "passive"))
      (node (ref "T45") (pin "2") (pinfunction "B_2") (pintype "passive"))
    )
    (net (code "5") (name "AC3") (class "Default")
      (node (ref "D40BOT") (pin "9") (pinfunction "1_9") (pintype "passive"))
      (node (ref "E40") (pin "14") (pinfunction "14_14") (pintype "passive"))
      (node (ref "T46") (pin "2") (pinfunction "B_2") (pintype "passive"))
    )
    (net (code "6") (name "AC4") (class "Default")
      (node (ref "D40TOP") (pin "17") (pinfunction "1_17") (pintype "passive"))
      (node (ref "E40") (pin "31") (pinfunction "31_31") (pintype "passive"))
      (node (ref "T47") (pin "2") (pinfunction "B_2") (pintype "passive"))
    )
    (net (code "7") (name "AC5") (class "Default")
      (node (ref "D40BOT") (pin "16") (pinfunction "1_16") (pintype "passive"))
      (node (ref "E40") (pin "28") (pinfunction "28_28") (pintype "passive"))
      (node (ref "T48") (pin "2") (pinfunction "B_2") (pintype "passive"))
    )
    (net (code "8") (name "AC6") (class "Default")
      (node (ref "E40TOP") (pin "4") (pinfunction "1_4") (pintype "passive"))
      (node (ref "F40") (pin "7") (pinfunction "7_7") (pintype "passive"))
      (node (ref "T49") (pin "2") (pinfunction "B_2") (pintype "passive"))
    )
    (net (code "9") (name "AC7") (class "Default")
      (node (ref "E40BOT") (pin "2") (pinfunction "1_2") (pintype "passive"))
      (node (ref "F40") (pin "4") (pinfunction "4_4") (pintype "passive"))
      (node (ref "T50") (pin "2") (pinfunction "B_2") (pintype "passive"))
    )
    (net (code "10") (name "AC8") (class "Default")
      (node (ref "E40TOP") (pin "12") (pinfunction "1_12") (pintype "passive"))
      (node (ref "F40") (pin "21") (pinfunction "21_21") (pintype "passive"))
      (node (ref "T51") (pin "2") (pinfunction "B_2") (pintype "passive"))
    )
    (net (code "11") (name "AC9") (class "Default")
      (node (ref "E40BOT") (pin "9") (pinfunction "1_9") (pintype "passive"))
      (node (ref "F40") (pin "14") (pinfunction "14_14") (pintype "passive"))
      (node (ref "T52") (pin "2") (pinfunction "B_2") (pintype "passive"))
    )
    (net (code "12") (name "AC10") (class "Default")
      (node (ref "E40TOP") (pin "17") (pinfunction "1_17") (pintype "passive"))
      (node (ref "F40") (pin "31") (pinfunction "31_31") (pintype "passive"))
      (node (ref "T53") (pin "2") (pinfunction "B_2") (pintype "passive"))
    )
    (net (code "13") (name "AC11") (class "Default")
      (node (ref "E40BOT") (pin "16") (pinfunction "1_16") (pintype "passive"))
      (node (ref "F40") (pin "28") (pinfunction "28_28") (pintype "passive"))
      (node (ref "T54") (pin "2") (pinfunction "B_2") (pintype "passive"))
    )
    (net (code "14") (name "AND") (class "Default")
      (node (ref "D40") (pin "2") (pinfunction "2_2") (pintype "passive"))
      (node (ref "F40BOT") (pin "1") (pinfunction "1_1") (pintype "passive"))
      (node (ref "T82") (pin "2") (pinfunction "B_2") (pintype "passive"))
    )
    (net (code "15") (name "BREAK") (class "Default")
      (node (ref "D40") (pin "22") (pinfunction "22_22") (pintype "passive"))
      (node (ref "F40BOT") (pin "12") (pinfunction "1_12") (pintype "passive"))
      (node (ref "T81") (pin "2") (pinfunction "B_2") (pintype "passive"))
    )
    (net (code "16") (name "CA") (class "Default")
      (node (ref "D40") (pin "32") (pinfunction "32_32") (pintype "passive"))
      (node (ref "F40BOT") (pin "18") (pinfunction "1_18") (pintype "passive"))
      (node (ref "T80") (pin "2") (pinfunction "B_2") (pintype "passive"))
    )
    (net (code "17") (name "DCA") (class "Default")
      (node (ref "D40") (pin "8") (pinfunction "8_8") (pintype "passive"))
      (node (ref "F40BOT") (pin "4") (pinfunction "1_4") (pintype "passive"))
      (node (ref "T85") (pin "2") (pinfunction "B_2") (pintype "passive"))
    )
    (net (code "18") (name "DEFER") (class "Default")
      (node (ref "D40") (pin "26") (pinfunction "26_26") (pintype "passive"))
      (node (ref "F40BOT") (pin "15") (pinfunction "1_15") (pintype "passive"))
      (node (ref "T78") (pin "2") (pinfunction "B_2") (pintype "passive"))
    )
    (net (code "19") (name "DF0") (class "Default")
      (node (ref "C40") (pin "1") (pinfunction "1_1") (pintype "passive"))
      (node (ref "C40TOP") (pin "1") (pinfunction "1_1") (pintype "passive"))
      (node (ref "T1") (pin "2") (pinfunction "B_2") (pintype "passive"))
    )
    (net (code "20") (name "DF1") (class "Default")
      (node (ref "C40") (pin "10") (pinfunction "10_10") (pintype "passive"))
      (node (ref "C40BOT") (pin "5") (pinfunction "1_5") (pintype "passive"))
      (node (ref "T2") (pin "2") (pinfunction "B_2") (pintype "passive"))
    )
    (net (code "21") (name "DF2") (class "Default")
      (node (ref "C40") (pin "11") (pinfunction "11_11") (pintype "passive"))
      (node (ref "C40TOP") (pin "6") (pinfunction "1_6") (pintype "passive"))
      (node (ref "T3") (pin "2") (pinfunction "B_2") (pintype "passive"))
    )
    (net (code "22") (name "EXECUTE") (class "Default")
      (node (ref "D40") (pin "28") (pinfunction "28_28") (pintype "passive"))
      (node (ref "F40BOT") (pin "16") (pinfunction "1_16") (pintype "passive"))
      (node (ref "T77") (pin "2") (pinfunction "B_2") (pintype "passive"))
    )
    (net (code "23") (name "FETCH") (class "Default")
      (node (ref "D40") (pin "24") (pinfunction "24_24") (pintype "passive"))
      (node (ref "F40BOT") (pin "14") (pinfunction "1_14") (pintype "passive"))
      (node (ref "T76") (pin "2") (pinfunction "B_2") (pintype "passive"))
    )
    (net (code "24") (name "GND") (class "Default")
      (node (ref "C40") (pin "17") (pinfunction "17_17") (pintype "passive"))
      (node (ref "C40") (pin "18") (pinfunction "18_18") (pintype "passive"))
      (node (ref "C40") (pin "19") (pinfunction "19_19") (pintype "passive"))
      (node (ref "C40") (pin "20") (pinfunction "20_20") (pintype "passive"))
      (node (ref "C40BOT") (pin "13") (pinfunction "1_13") (pintype "passive"))
      (node (ref "D40") (pin "17") (pinfunction "17_17") (pintype "passive"))
      (node (ref "D40") (pin "18") (pinfunction "18_18") (pintype "passive"))
      (node (ref "D40") (pin "19") (pinfunction "19_19") (pintype "passive"))
      (node (ref "D40") (pin "20") (pinfunction "20_20") (pintype "passive"))
      (node (ref "D40BOT") (pin "13") (pinfunction "1_13") (pintype "passive"))
      (node (ref "E40") (pin "17") (pinfunction "17_17") (pintype "passive"))
      (node (ref "E40") (pin "18") (pinfunction "18_18") (pintype "passive"))
      (node (ref "E40") (pin "19") (pinfunction "19_19") (pintype "passive"))
      (node (ref "E40") (pin "20") (pinfunction "20_20") (pintype "passive"))
      (node (ref "E40BOT") (pin "13") (pinfunction "1_13") (pintype "passive"))
      (node (ref "F40") (pin "17") (pinfunction "17_17") (pintype "passive"))
      (node (ref "F40") (pin "18") (pinfunction "18_18") (pintype "passive"))
      (node (ref "F40") (pin "19") (pinfunction "19_19") (pintype "passive"))
      (node (ref "F40") (pin "20") (pinfunction "20_20") (pintype "passive"))
      (node (ref "F40BOT") (pin "13") (pinfunction "1_13") (pintype "passive"))
      (node (ref "GND1") (pin "1") (pinfunction "KL_1") (pintype "passive"))
      (node (ref "GND1") (pin "2") (pinfunction "KL_2") (pintype "passive"))
      (node (ref "GND2") (pin "1") (pinfunction "KL_1") (pintype "passive"))
      (node (ref "GND2") (pin "2") (pinfunction "KL_2") (pintype "passive"))
      (node (ref "PAD3") (pin "1") (pinfunction "P_1") (pintype "passive"))
      (node (ref "PAD4") (pin "1") (pinfunction "P_1") (pintype "passive"))
      (node (ref "T1") (pin "1") (pinfunction "E_1") (pintype "passive"))
      (node (ref "T10") (pin "1") (pinfunction "E_1") (pintype "passive"))
      (node (ref "T11") (pin "1") (pinfunction "E_1") (pintype "passive"))
      (node (ref "T12") (pin "1") (pinfunction "E_1") (pintype "passive"))
      (node (ref "T13") (pin "1") (pinfunction "E_1") (pintype "passive"))
      (node (ref "T14") (pin "1") (pinfunction "E_1") (pintype "passive"))
      (node (ref "T15") (pin "1") (pinfunction "E_1") (pintype "passive"))
      (node (ref "T16") (pin "1") (pinfunction "E_1") (pintype "passive"))
      (node (ref "T17") (pin "1") (pinfunction "E_1") (pintype "passive"))
      (node (ref "T18") (pin "1") (pinfunction "E_1") (pintype "passive"))
      (node (ref "T19") (pin "1") (pinfunction "E_1") (pintype "passive"))
      (node (ref "T2") (pin "1") (pinfunction "E_1") (pintype "passive"))
      (node (ref "T20") (pin "1") (pinfunction "E_1") (pintype "passive"))
      (node (ref "T21") (pin "1") (pinfunction "E_1") (pintype "passive"))
      (node (ref "T22") (pin "1") (pinfunction "E_1") (pintype "passive"))
      (node (ref "T23") (pin "1") (pinfunction "E_1") (pintype "passive"))
      (node (ref "T24") (pin "1") (pinfunction "E_1") (pintype "passive"))
      (node (ref "T25") (pin "1") (pinfunction "E_1") (pintype "passive"))
      (node (ref "T26") (pin "1") (pinfunction "E_1") (pintype "passive"))
      (node (ref "T27") (pin "1") (pinfunction "E_1") (pintype "passive"))
      (node (ref "T28") (pin "1") (pinfunction "E_1") (pintype "passive"))
      (node (ref "T29") (pin "1") (pinfunction "E_1") (pintype "passive"))
      (node (ref "T3") (pin "1") (pinfunction "E_1") (pintype "passive"))
      (node (ref "T30") (pin "1") (pinfunction "E_1") (pintype "passive"))
      (node (ref "T31") (pin "1") (pinfunction "E_1") (pintype "passive"))
      (node (ref "T32") (pin "1") (pinfunction "E_1") (pintype "passive"))
      (node (ref "T33") (pin "1") (pinfunction "E_1") (pintype "passive"))
      (node (ref "T34") (pin "1") (pinfunction "E_1") (pintype "passive"))
      (node (ref "T35") (pin "1") (pinfunction "E_1") (pintype "passive"))
      (node (ref "T36") (pin "1") (pinfunction "E_1") (pintype "passive"))
      (node (ref "T37") (pin "1") (pinfunction "E_1") (pintype "passive"))
      (node (ref "T38") (pin "1") (pinfunction "E_1") (pintype "passive"))
      (node (ref "T39") (pin "1") (pinfunction "E_1") (pintype "passive"))
      (node (ref "T4") (pin "1") (pinfunction "E_1") (pintype "passive"))
      (node (ref "T40") (pin "1") (pinfunction "E_1") (pintype "passive"))
      (node (ref "T41") (pin "1") (pinfunction "E_1") (pintype "passive"))
      (node (ref "T42") (pin "1") (pinfunction "E_1") (pintype "passive"))
      (node (ref "T43") (pin "1") (pinfunction "E_1") (pintype "passive"))
      (node (ref "T44") (pin "1") (pinfunction "E_1") (pintype "passive"))
      (node (ref "T45") (pin "1") (pinfunction "E_1") (pintype "passive"))
      (node (ref "T46") (pin "1") (pinfunction "E_1") (pintype "passive"))
      (node (ref "T47") (pin "1") (pinfunction "E_1") (pintype "passive"))
      (node (ref "T48") (pin "1") (pinfunction "E_1") (pintype "passive"))
      (node (ref "T49") (pin "1") (pinfunction "E_1") (pintype "passive"))
      (node (ref "T5") (pin "1") (pinfunction "E_1") (pintype "passive"))
      (node (ref "T50") (pin "1") (pinfunction "E_1") (pintype "passive"))
      (node (ref "T51") (pin "1") (pinfunction "E_1") (pintype "passive"))
      (node (ref "T52") (pin "1") (pinfunction "E_1") (pintype "passive"))
      (node (ref "T53") (pin "1") (pinfunction "E_1") (pintype "passive"))
      (node (ref "T54") (pin "1") (pinfunction "E_1") (pintype "passive"))
      (node (ref "T55") (pin "1") (pinfunction "E_1") (pintype "passive"))
      (node (ref "T56") (pin "1") (pinfunction "E_1") (pintype "passive"))
      (node (ref "T57") (pin "1") (pinfunction "E_1") (pintype "passive"))
      (node (ref "T58") (pin "1") (pinfunction "E_1") (pintype "passive"))
      (node (ref "T59") (pin "1") (pinfunction "E_1") (pintype "passive"))
      (node (ref "T6") (pin "1") (pinfunction "E_1") (pintype "passive"))
      (node (ref "T60") (pin "1") (pinfunction "E_1") (pintype "passive"))
      (node (ref "T61") (pin "1") (pinfunction "E_1") (pintype "passive"))
      (node (ref "T62") (pin "1") (pinfunction "E_1") (pintype "passive"))
      (node (ref "T63") (pin "1") (pinfunction "E_1") (pintype "passive"))
      (node (ref "T64") (pin "1") (pinfunction "E_1") (pintype "passive"))
      (node (ref "T65") (pin "1") (pinfunction "E_1") (pintype "passive"))
      (node (ref "T66") (pin "1") (pinfunction "E_1") (pintype "passive"))
      (node (ref "T67") (pin "1") (pinfunction "E_1") (pintype "passive"))
      (node (ref "T68") (pin "1") (pinfunction "E_1") (pintype "passive"))
      (node (ref "T69") (pin "1") (pinfunction "E_1") (pintype "passive"))
      (node (ref "T7") (pin "1") (pinfunction "E_1") (pintype "passive"))
      (node (ref "T70") (pin "1") (pinfunction "E_1") (pintype "passive"))
      (node (ref "T71") (pin "1") (pinfunction "E_1") (pintype "passive"))
      (node (ref "T72") (pin "1") (pinfunction "E_1") (pintype "passive"))
      (node (ref "T73") (pin "1") (pinfunction "E_1") (pintype "passive"))
      (node (ref "T74") (pin "1") (pinfunction "E_1") (pintype "passive"))
      (node (ref "T75") (pin "1") (pinfunction "E_1") (pintype "passive"))
      (node (ref "T76") (pin "1") (pinfunction "E_1") (pintype "passive"))
      (node (ref "T77") (pin "1") (pinfunction "E_1") (pintype "passive"))
      (node (ref "T78") (pin "1") (pinfunction "E_1") (pintype "passive"))
      (node (ref "T79") (pin "1") (pinfunction "E_1") (pintype "passive"))
      (node (ref "T8") (pin "1") (pinfunction "E_1") (pintype "passive"))
      (node (ref "T80") (pin "1") (pinfunction "E_1") (pintype "passive"))
      (node (ref "T81") (pin "1") (pinfunction "E_1") (pintype "passive"))
      (node (ref "T82") (pin "1") (pinfunction "E_1") (pintype "passive"))
      (node (ref "T83") (pin "1") (pinfunction "E_1") (pintype "passive"))
      (node (ref "T84") (pin "1") (pinfunction "E_1") (pintype "passive"))
      (node (ref "T85") (pin "1") (pinfunction "E_1") (pintype "passive"))
      (node (ref "T86") (pin "1") (pinfunction "E_1") (pintype "passive"))
      (node (ref "T87") (pin "1") (pinfunction "E_1") (pintype "passive"))
      (node (ref "T88") (pin "1") (pinfunction "E_1") (pintype "passive"))
      (node (ref "T89") (pin "1") (pinfunction "E_1") (pintype "passive"))
      (node (ref "T9") (pin "1") (pinfunction "E_1") (pintype "passive"))
      (node (ref "X3") (pin "1") (pinfunction "KL_1") (pintype "passive"))
      (node (ref "X3") (pin "2") (pinfunction "KL_2") (pintype "passive"))
      (node (ref "X4") (pin "1") (pinfunction "KL_1") (pintype "passive"))
      (node (ref "X4") (pin "2") (pinfunction "KL_2") (pintype "passive"))
    )
    (net (code "25") (name "IF0") (class "Default")
      (node (ref "C40") (pin "24") (pinfunction "24_24") (pintype "passive"))
      (node (ref "C40BOT") (pin "14") (pinfunction "1_14") (pintype "passive"))
      (node (ref "T4") (pin "2") (pinfunction "B_2") (pintype "passive"))
    )
    (net (code "26") (name "IF1") (class "Default")
      (node (ref "C40") (pin "25") (pinfunction "25_25") (pintype "passive"))
      (node (ref "C40TOP") (pin "14") (pinfunction "1_14") (pintype "passive"))
      (node (ref "T5") (pin "2") (pinfunction "B_2") (pintype "passive"))
    )
    (net (code "27") (name "IF2") (class "Default")
      (node (ref "C40") (pin "34") (pinfunction "34_34") (pintype "passive"))
      (node (ref "C40BOT") (pin "19") (pinfunction "1_19") (pintype "passive"))
      (node (ref "T6") (pin "2") (pinfunction "B_2") (pintype "passive"))
    )
    (net (code "28") (name "ION") (class "Default")
      (node (ref "D40") (pin "34") (pinfunction "34_34") (pintype "passive"))
      (node (ref "F40BOT") (pin "19") (pinfunction "1_19") (pintype "passive"))
      (node (ref "T73") (pin "2") (pinfunction "B_2") (pintype "passive"))
    )
    (net (code "29") (name "IOT") (class "Default")
      (node (ref "D40") (pin "23") (pinfunction "23_23") (pintype "passive"))
      (node (ref "F40TOP") (pin "13") (pinfunction "1_13") (pintype "passive"))
      (node (ref "T88") (pin "2") (pinfunction "B_2") (pintype "passive"))
    )
    (net (code "30") (name "ISZ") (class "Default")
      (node (ref "D40") (pin "6") (pinfunction "6_6") (pintype "passive"))
      (node (ref "F40BOT") (pin "3") (pinfunction "1_3") (pintype "passive"))
      (node (ref "T84") (pin "2") (pinfunction "B_2") (pintype "passive"))
    )
    (net (code "31") (name "JMP") (class "Default")
      (node (ref "D40") (pin "12") (pinfunction "12_12") (pintype "passive"))
      (node (ref "F40BOT") (pin "6") (pinfunction "1_6") (pintype "passive"))
      (node (ref "T87") (pin "2") (pinfunction "B_2") (pintype "passive"))
    )
    (net (code "32") (name "JMS") (class "Default")
      (node (ref "D40") (pin "10") (pinfunction "10_10") (pintype "passive"))
      (node (ref "F40BOT") (pin "5") (pinfunction "1_5") (pintype "passive"))
      (node (ref "T86") (pin "2") (pinfunction "B_2") (pintype "passive"))
    )
    (net (code "33") (name "LINK") (class "Default")
      (node (ref "C40") (pin "28") (pinfunction "28_28") (pintype "passive"))
      (node (ref "C40BOT") (pin "16") (pinfunction "1_16") (pintype "passive"))
      (node (ref "T72") (pin "2") (pinfunction "B_2") (pintype "passive"))
    )
    (net (code "34") (name "MA0") (class "Default")
      (node (ref "D40TOP") (pin "2") (pinfunction "1_2") (pintype "passive"))
      (node (ref "E40") (pin "3") (pinfunction "3_3") (pintype "passive"))
      (node (ref "T19") (pin "2") (pinfunction "B_2") (pintype "passive"))
    )
    (net (code "35") (name "MA1") (class "Default")
      (node (ref "D40BOT") (pin "4") (pinfunction "1_4") (pintype "passive"))
      (node (ref "E40") (pin "8") (pinfunction "8_8") (pintype "passive"))
      (node (ref "T20") (pin "2") (pinfunction "B_2") (pintype "passive"))
    )
    (net (code "36") (name "MA2") (class "Default")
      (node (ref "D40TOP") (pin "7") (pinfunction "1_7") (pintype "passive"))
      (node (ref "E40") (pin "13") (pinfunction "13_13") (pintype "passive"))
      (node (ref "T21") (pin "2") (pinfunction "B_2") (pintype "passive"))
    )
    (net (code "37") (name "MA3") (class "Default")
      (node (ref "D40BOT") (pin "12") (pinfunction "1_12") (pintype "passive"))
      (node (ref "E40") (pin "22") (pinfunction "22_22") (pintype "passive"))
      (node (ref "T22") (pin "2") (pinfunction "B_2") (pintype "passive"))
    )
    (net (code "38") (name "MA4") (class "Default")
      (node (ref "D40TOP") (pin "15") (pinfunction "1_15") (pintype "passive"))
      (node (ref "E40") (pin "27") (pinfunction "27_27") (pintype "passive"))
      (node (ref "T23") (pin "2") (pinfunction "B_2") (pintype "passive"))
    )
    (net (code "39") (name "MA5") (class "Default")
      (node (ref "D40BOT") (pin "18") (pinfunction "1_18") (pintype "passive"))
      (node (ref "E40") (pin "32") (pinfunction "32_32") (pintype "passive"))
      (node (ref "T24") (pin "2") (pinfunction "B_2") (pintype "passive"))
    )
    (net (code "40") (name "MA6") (class "Default")
      (node (ref "E40TOP") (pin "2") (pinfunction "1_2") (pintype "passive"))
      (node (ref "F40") (pin "3") (pinfunction "3_3") (pintype "passive"))
      (node (ref "T25") (pin "2") (pinfunction "B_2") (pintype "passive"))
    )
    (net (code "41") (name "MA7") (class "Default")
      (node (ref "E40BOT") (pin "4") (pinfunction "1_4") (pintype "passive"))
      (node (ref "F40") (pin "8") (pinfunction "8_8") (pintype "passive"))
      (node (ref "T26") (pin "2") (pinfunction "B_2") (pintype "passive"))
    )
    (net (code "42") (name "MA8") (class "Default")
      (node (ref "E40TOP") (pin "7") (pinfunction "1_7") (pintype "passive"))
      (node (ref "F40") (pin "13") (pinfunction "13_13") (pintype "passive"))
      (node (ref "T27") (pin "2") (pinfunction "B_2") (pintype "passive"))
    )
    (net (code "43") (name "MA9") (class "Default")
      (node (ref "E40BOT") (pin "12") (pinfunction "1_12") (pintype "passive"))
      (node (ref "F40") (pin "22") (pinfunction "22_22") (pintype "passive"))
      (node (ref "T28") (pin "2") (pinfunction "B_2") (pintype "passive"))
    )
    (net (code "44") (name "MA10") (class "Default")
      (node (ref "E40TOP") (pin "15") (pinfunction "1_15") (pintype "passive"))
      (node (ref "F40") (pin "27") (pinfunction "27_27") (pintype "passive"))
      (node (ref "T29") (pin "2") (pinfunction "B_2") (pintype "passive"))
    )
    (net (code "45") (name "MA11") (class "Default")
      (node (ref "E40BOT") (pin "18") (pinfunction "1_18") (pintype "passive"))
      (node (ref "F40") (pin "32") (pinfunction "32_32") (pintype "passive"))
      (node (ref "T30") (pin "2") (pinfunction "B_2") (pintype "passive"))
    )
    (net (code "46") (name "MB0") (class "Default")
      (node (ref "D40TOP") (pin "3") (pinfunction "1_3") (pintype "passive"))
      (node (ref "E40") (pin "5") (pinfunction "5_5") (pintype "passive"))
      (node (ref "T31") (pin "2") (pinfunction "B_2") (pintype "passive"))
    )
    (net (code "47") (name "MB1") (class "Default")
      (node (ref "D40BOT") (pin "3") (pinfunction "1_3") (pintype "passive"))
      (node (ref "E40") (pin "6") (pinfunction "6_6") (pintype "passive"))
      (node (ref "T32") (pin "2") (pinfunction "B_2") (pintype "passive"))
    )
    (net (code "48") (name "MB2") (class "Default")
      (node (ref "D40TOP") (pin "8") (pinfunction "1_8") (pintype "passive"))
      (node (ref "E40") (pin "15") (pinfunction "15_15") (pintype "passive"))
      (node (ref "T33") (pin "2") (pinfunction "B_2") (pintype "passive"))
    )
    (net (code "49") (name "MB3") (class "Default")
      (node (ref "D40BOT") (pin "11") (pinfunction "1_11") (pintype "passive"))
      (node (ref "E40") (pin "16") (pinfunction "16_16") (pintype "passive"))
      (node (ref "T34") (pin "2") (pinfunction "B_2") (pintype "passive"))
    )
    (net (code "50") (name "MB4") (class "Default")
      (node (ref "D40TOP") (pin "16") (pinfunction "1_16") (pintype "passive"))
      (node (ref "E40") (pin "29") (pinfunction "29_29") (pintype "passive"))
      (node (ref "T35") (pin "2") (pinfunction "B_2") (pintype "passive"))
    )
    (net (code "51") (name "MB5") (class "Default")
      (node (ref "D40BOT") (pin "17") (pinfunction "1_17") (pintype "passive"))
      (node (ref "E40") (pin "30") (pinfunction "30_30") (pintype "passive"))
      (node (ref "T36") (pin "2") (pinfunction "B_2") (pintype "passive"))
    )
    (net (code "52") (name "MB6") (class "Default")
      (node (ref "E40TOP") (pin "3") (pinfunction "1_3") (pintype "passive"))
      (node (ref "F40") (pin "5") (pinfunction "5_5") (pintype "passive"))
      (node (ref "T37") (pin "2") (pinfunction "B_2") (pintype "passive"))
    )
    (net (code "53") (name "MB7") (class "Default")
      (node (ref "E40BOT") (pin "3") (pinfunction "1_3") (pintype "passive"))
      (node (ref "F40") (pin "6") (pinfunction "6_6") (pintype "passive"))
      (node (ref "T38") (pin "2") (pinfunction "B_2") (pintype "passive"))
    )
    (net (code "54") (name "MB8") (class "Default")
      (node (ref "E40TOP") (pin "8") (pinfunction "1_8") (pintype "passive"))
      (node (ref "F40") (pin "15") (pinfunction "15_15") (pintype "passive"))
      (node (ref "T39") (pin "2") (pinfunction "B_2") (pintype "passive"))
    )
    (net (code "55") (name "MB9") (class "Default")
      (node (ref "E40BOT") (pin "11") (pinfunction "1_11") (pintype "passive"))
      (node (ref "F40") (pin "16") (pinfunction "16_16") (pintype "passive"))
      (node (ref "T40") (pin "2") (pinfunction "B_2") (pintype "passive"))
    )
    (net (code "56") (name "MB10") (class "Default")
      (node (ref "E40TOP") (pin "16") (pinfunction "1_16") (pintype "passive"))
      (node (ref "F40") (pin "29") (pinfunction "29_29") (pintype "passive"))
      (node (ref "T41") (pin "2") (pinfunction "B_2") (pintype "passive"))
    )
    (net (code "57") (name "MB11") (class "Default")
      (node (ref "E40BOT") (pin "17") (pinfunction "1_17") (pintype "passive"))
      (node (ref "F40") (pin "30") (pinfunction "30_30") (pintype "passive"))
      (node (ref "T42") (pin "2") (pinfunction "B_2") (pintype "passive"))
    )
    (net (code "58") (name "MQ0") (class "Default")
      (node (ref "D40TOP") (pin "5") (pinfunction "1_5") (pintype "passive"))
      (node (ref "E40") (pin "9") (pinfunction "9_9") (pintype "passive"))
      (node (ref "T55") (pin "2") (pinfunction "B_2") (pintype "passive"))
    )
    (net (code "59") (name "MQ1") (class "Default")
      (node (ref "D40BOT") (pin "1") (pinfunction "1_1") (pintype "passive"))
      (node (ref "E40") (pin "2") (pinfunction "2_2") (pintype "passive"))
      (node (ref "T56") (pin "2") (pinfunction "B_2") (pintype "passive"))
    )
    (net (code "60") (name "MQ2") (class "Default")
      (node (ref "D40TOP") (pin "13") (pinfunction "1_13") (pintype "passive"))
      (node (ref "E40") (pin "23") (pinfunction "23_23") (pintype "passive"))
      (node (ref "T57") (pin "2") (pinfunction "B_2") (pintype "passive"))
    )
    (net (code "61") (name "MQ3") (class "Default")
      (node (ref "D40BOT") (pin "6") (pinfunction "1_6") (pintype "passive"))
      (node (ref "E40") (pin "12") (pinfunction "12_12") (pintype "passive"))
      (node (ref "T58") (pin "2") (pinfunction "B_2") (pintype "passive"))
    )
    (net (code "62") (name "MQ4") (class "Default")
      (node (ref "D40TOP") (pin "18") (pinfunction "1_18") (pintype "passive"))
      (node (ref "E40") (pin "33") (pinfunction "33_33") (pintype "passive"))
      (node (ref "T59") (pin "2") (pinfunction "B_2") (pintype "passive"))
    )
    (net (code "63") (name "MQ5") (class "Default")
      (node (ref "D40BOT") (pin "15") (pinfunction "1_15") (pintype "passive"))
      (node (ref "E40") (pin "26") (pinfunction "26_26") (pintype "passive"))
      (node (ref "T60") (pin "2") (pinfunction "B_2") (pintype "passive"))
    )
    (net (code "64") (name "MQ6") (class "Default")
      (node (ref "E40TOP") (pin "5") (pinfunction "1_5") (pintype "passive"))
      (node (ref "F40") (pin "9") (pinfunction "9_9") (pintype "passive"))
      (node (ref "T61") (pin "2") (pinfunction "B_2") (pintype "passive"))
    )
    (net (code "65") (name "MQ7") (class "Default")
      (node (ref "E40BOT") (pin "1") (pinfunction "1_1") (pintype "passive"))
      (node (ref "F40") (pin "2") (pinfunction "2_2") (pintype "passive"))
      (node (ref "T62") (pin "2") (pinfunction "B_2") (pintype "passive"))
    )
    (net (code "66") (name "MQ8") (class "Default")
      (node (ref "E40TOP") (pin "13") (pinfunction "1_13") (pintype "passive"))
      (node (ref "F40") (pin "23") (pinfunction "23_23") (pintype "passive"))
      (node (ref "T63") (pin "2") (pinfunction "B_2") (pintype "passive"))
    )
    (net (code "67") (name "MQ9") (class "Default")
      (node (ref "E40BOT") (pin "6") (pinfunction "1_6") (pintype "passive"))
      (node (ref "F40") (pin "12") (pinfunction "12_12") (pintype "passive"))
      (node (ref "T64") (pin "2") (pinfunction "B_2") (pintype "passive"))
    )
    (net (code "68") (name "MQ10") (class "Default")
      (node (ref "E40TOP") (pin "18") (pinfunction "1_18") (pintype "passive"))
      (node (ref "F40") (pin "33") (pinfunction "33_33") (pintype "passive"))
      (node (ref "T65") (pin "2") (pinfunction "B_2") (pintype "passive"))
    )
    (net (code "69") (name "MQ11") (class "Default")
      (node (ref "E40BOT") (pin "15") (pinfunction "1_15") (pintype "passive"))
      (node (ref "F40") (pin "26") (pinfunction "26_26") (pintype "passive"))
      (node (ref "T66") (pin "2") (pinfunction "B_2") (pintype "passive"))
    )
    (net (code "70") (name "Net-(T1-C)") (class "Default")
      (node (ref "DF0") (pin "B") (pinfunction "B_B") (pintype "passive"))
      (node (ref "T1") (pin "3") (pinfunction "C_3") (pintype "passive"))
    )
    (net (code "71") (name "Net-(T2-C)") (class "Default")
      (node (ref "DF1") (pin "B") (pinfunction "B_B") (pintype "passive"))
      (node (ref "T2") (pin "3") (pinfunction "C_3") (pintype "passive"))
    )
    (net (code "72") (name "Net-(T3-C)") (class "Default")
      (node (ref "DF2") (pin "B") (pinfunction "B_B") (pintype "passive"))
      (node (ref "T3") (pin "3") (pinfunction "C_3") (pintype "passive"))
    )
    (net (code "73") (name "Net-(T4-C)") (class "Default")
      (node (ref "IF0") (pin "B") (pinfunction "B_B") (pintype "passive"))
      (node (ref "T4") (pin "3") (pinfunction "C_3") (pintype "passive"))
    )
    (net (code "74") (name "Net-(T5-C)") (class "Default")
      (node (ref "IF1") (pin "B") (pinfunction "B_B") (pintype "passive"))
      (node (ref "T5") (pin "3") (pinfunction "C_3") (pintype "passive"))
    )
    (net (code "75") (name "Net-(T6-C)") (class "Default")
      (node (ref "IF2") (pin "B") (pinfunction "B_B") (pintype "passive"))
      (node (ref "T6") (pin "3") (pinfunction "C_3") (pintype "passive"))
    )
    (net (code "76") (name "Net-(T7-C)") (class "Default")
      (node (ref "PC0") (pin "B") (pinfunction "B_B") (pintype "passive"))
      (node (ref "T7") (pin "3") (pinfunction "C_3") (pintype "passive"))
    )
    (net (code "77") (name "Net-(T8-C)") (class "Default")
      (node (ref "PC1") (pin "B") (pinfunction "B_B") (pintype "passive"))
      (node (ref "T8") (pin "3") (pinfunction "C_3") (pintype "passive"))
    )
    (net (code "78") (name "Net-(T9-C)") (class "Default")
      (node (ref "PC2") (pin "B") (pinfunction "B_B") (pintype "passive"))
      (node (ref "T9") (pin "3") (pinfunction "C_3") (pintype "passive"))
    )
    (net (code "79") (name "Net-(T10-C)") (class "Default")
      (node (ref "PC3") (pin "B") (pinfunction "B_B") (pintype "passive"))
      (node (ref "T10") (pin "3") (pinfunction "C_3") (pintype "passive"))
    )
    (net (code "80") (name "Net-(T11-C)") (class "Default")
      (node (ref "PC4") (pin "B") (pinfunction "B_B") (pintype "passive"))
      (node (ref "T11") (pin "3") (pinfunction "C_3") (pintype "passive"))
    )
    (net (code "81") (name "Net-(T12-C)") (class "Default")
      (node (ref "PC5") (pin "B") (pinfunction "B_B") (pintype "passive"))
      (node (ref "T12") (pin "3") (pinfunction "C_3") (pintype "passive"))
    )
    (net (code "82") (name "Net-(T13-C)") (class "Default")
      (node (ref "PC6") (pin "B") (pinfunction "B_B") (pintype "passive"))
      (node (ref "T13") (pin "3") (pinfunction "C_3") (pintype "passive"))
    )
    (net (code "83") (name "Net-(T14-C)") (class "Default")
      (node (ref "PC7") (pin "B") (pinfunction "B_B") (pintype "passive"))
      (node (ref "T14") (pin "3") (pinfunction "C_3") (pintype "passive"))
    )
    (net (code "84") (name "Net-(T15-C)") (class "Default")
      (node (ref "PC8") (pin "B") (pinfunction "B_B") (pintype "passive"))
      (node (ref "T15") (pin "3") (pinfunction "C_3") (pintype "passive"))
    )
    (net (code "85") (name "Net-(T16-C)") (class "Default")
      (node (ref "PC9") (pin "B") (pinfunction "B_B") (pintype "passive"))
      (node (ref "T16") (pin "3") (pinfunction "C_3") (pintype "passive"))
    )
    (net (code "86") (name "Net-(T17-C)") (class "Default")
      (node (ref "PC10") (pin "B") (pinfunction "B_B") (pintype "passive"))
      (node (ref "T17") (pin "3") (pinfunction "C_3") (pintype "passive"))
    )
    (net (code "87") (name "Net-(T18-C)") (class "Default")
      (node (ref "PC11") (pin "B") (pinfunction "B_B") (pintype "passive"))
      (node (ref "T18") (pin "3") (pinfunction "C_3") (pintype "passive"))
    )
    (net (code "88") (name "Net-(T19-C)") (class "Default")
      (node (ref "MA0") (pin "B") (pinfunction "B_B") (pintype "passive"))
      (node (ref "T19") (pin "3") (pinfunction "C_3") (pintype "passive"))
    )
    (net (code "89") (name "Net-(T20-C)") (class "Default")
      (node (ref "MA1") (pin "B") (pinfunction "B_B") (pintype "passive"))
      (node (ref "T20") (pin "3") (pinfunction "C_3") (pintype "passive"))
    )
    (net (code "90") (name "Net-(T21-C)") (class "Default")
      (node (ref "MA2") (pin "B") (pinfunction "B_B") (pintype "passive"))
      (node (ref "T21") (pin "3") (pinfunction "C_3") (pintype "passive"))
    )
    (net (code "91") (name "Net-(T22-C)") (class "Default")
      (node (ref "MA3") (pin "B") (pinfunction "B_B") (pintype "passive"))
      (node (ref "T22") (pin "3") (pinfunction "C_3") (pintype "passive"))
    )
    (net (code "92") (name "Net-(T23-C)") (class "Default")
      (node (ref "MA4") (pin "B") (pinfunction "B_B") (pintype "passive"))
      (node (ref "T23") (pin "3") (pinfunction "C_3") (pintype "passive"))
    )
    (net (code "93") (name "Net-(T24-C)") (class "Default")
      (node (ref "MA5") (pin "B") (pinfunction "B_B") (pintype "passive"))
      (node (ref "T24") (pin "3") (pinfunction "C_3") (pintype "passive"))
    )
    (net (code "94") (name "Net-(T25-C)") (class "Default")
      (node (ref "MA6") (pin "B") (pinfunction "B_B") (pintype "passive"))
      (node (ref "T25") (pin "3") (pinfunction "C_3") (pintype "passive"))
    )
    (net (code "95") (name "Net-(T26-C)") (class "Default")
      (node (ref "MA7") (pin "B") (pinfunction "B_B") (pintype "passive"))
      (node (ref "T26") (pin "3") (pinfunction "C_3") (pintype "passive"))
    )
    (net (code "96") (name "Net-(T27-C)") (class "Default")
      (node (ref "MA8") (pin "B") (pinfunction "B_B") (pintype "passive"))
      (node (ref "T27") (pin "3") (pinfunction "C_3") (pintype "passive"))
    )
    (net (code "97") (name "Net-(T28-C)") (class "Default")
      (node (ref "MA9") (pin "B") (pinfunction "B_B") (pintype "passive"))
      (node (ref "T28") (pin "3") (pinfunction "C_3") (pintype "passive"))
    )
    (net (code "98") (name "Net-(T29-C)") (class "Default")
      (node (ref "MA10") (pin "B") (pinfunction "B_B") (pintype "passive"))
      (node (ref "T29") (pin "3") (pinfunction "C_3") (pintype "passive"))
    )
    (net (code "99") (name "Net-(T30-C)") (class "Default")
      (node (ref "MA11") (pin "B") (pinfunction "B_B") (pintype "passive"))
      (node (ref "T30") (pin "3") (pinfunction "C_3") (pintype "passive"))
    )
    (net (code "100") (name "Net-(T31-C)") (class "Default")
      (node (ref "MB0") (pin "B") (pinfunction "B_B") (pintype "passive"))
      (node (ref "T31") (pin "3") (pinfunction "C_3") (pintype "passive"))
    )
    (net (code "101") (name "Net-(T32-C)") (class "Default")
      (node (ref "MB1") (pin "B") (pinfunction "B_B") (pintype "passive"))
      (node (ref "T32") (pin "3") (pinfunction "C_3") (pintype "passive"))
    )
    (net (code "102") (name "Net-(T33-C)") (class "Default")
      (node (ref "MB2") (pin "B") (pinfunction "B_B") (pintype "passive"))
      (node (ref "T33") (pin "3") (pinfunction "C_3") (pintype "passive"))
    )
    (net (code "103") (name "Net-(T34-C)") (class "Default")
      (node (ref "MB3") (pin "B") (pinfunction "B_B") (pintype "passive"))
      (node (ref "T34") (pin "3") (pinfunction "C_3") (pintype "passive"))
    )
    (net (code "104") (name "Net-(T35-C)") (class "Default")
      (node (ref "MB4") (pin "B") (pinfunction "B_B") (pintype "passive"))
      (node (ref "T35") (pin "3") (pinfunction "C_3") (pintype "passive"))
    )
    (net (code "105") (name "Net-(T36-C)") (class "Default")
      (node (ref "MB5") (pin "B") (pinfunction "B_B") (pintype "passive"))
      (node (ref "T36") (pin "3") (pinfunction "C_3") (pintype "passive"))
    )
    (net (code "106") (name "Net-(T37-C)") (class "Default")
      (node (ref "MB6") (pin "B") (pinfunction "B_B") (pintype "passive"))
      (node (ref "T37") (pin "3") (pinfunction "C_3") (pintype "passive"))
    )
    (net (code "107") (name "Net-(T38-C)") (class "Default")
      (node (ref "MB7") (pin "B") (pinfunction "B_B") (pintype "passive"))
      (node (ref "T38") (pin "3") (pinfunction "C_3") (pintype "passive"))
    )
    (net (code "108") (name "Net-(T39-C)") (class "Default")
      (node (ref "MB8") (pin "B") (pinfunction "B_B") (pintype "passive"))
      (node (ref "T39") (pin "3") (pinfunction "C_3") (pintype "passive"))
    )
    (net (code "109") (name "Net-(T40-C)") (class "Default")
      (node (ref "MB9") (pin "B") (pinfunction "B_B") (pintype "passive"))
      (node (ref "T40") (pin "3") (pinfunction "C_3") (pintype "passive"))
    )
    (net (code "110") (name "Net-(T41-C)") (class "Default")
      (node (ref "MB10") (pin "B") (pinfunction "B_B") (pintype "passive"))
      (node (ref "T41") (pin "3") (pinfunction "C_3") (pintype "passive"))
    )
    (net (code "111") (name "Net-(T42-C)") (class "Default")
      (node (ref "MB11") (pin "B") (pinfunction "B_B") (pintype "passive"))
      (node (ref "T42") (pin "3") (pinfunction "C_3") (pintype "passive"))
    )
    (net (code "112") (name "Net-(T43-C)") (class "Default")
      (node (ref "AC0") (pin "B") (pinfunction "B_B") (pintype "passive"))
      (node (ref "T43") (pin "3") (pinfunction "C_3") (pintype "passive"))
    )
    (net (code "113") (name "Net-(T44-C)") (class "Default")
      (node (ref "AC1") (pin "B") (pinfunction "B_B") (pintype "passive"))
      (node (ref "T44") (pin "3") (pinfunction "C_3") (pintype "passive"))
    )
    (net (code "114") (name "Net-(T45-C)") (class "Default")
      (node (ref "AC2") (pin "B") (pinfunction "B_B") (pintype "passive"))
      (node (ref "T45") (pin "3") (pinfunction "C_3") (pintype "passive"))
    )
    (net (code "115") (name "Net-(T46-C)") (class "Default")
      (node (ref "AC3") (pin "B") (pinfunction "B_B") (pintype "passive"))
      (node (ref "T46") (pin "3") (pinfunction "C_3") (pintype "passive"))
    )
    (net (code "116") (name "Net-(T47-C)") (class "Default")
      (node (ref "AC4") (pin "B") (pinfunction "B_B") (pintype "passive"))
      (node (ref "T47") (pin "3") (pinfunction "C_3") (pintype "passive"))
    )
    (net (code "117") (name "Net-(T48-C)") (class "Default")
      (node (ref "AC5") (pin "B") (pinfunction "B_B") (pintype "passive"))
      (node (ref "T48") (pin "3") (pinfunction "C_3") (pintype "passive"))
    )
    (net (code "118") (name "Net-(T49-C)") (class "Default")
      (node (ref "AC6") (pin "B") (pinfunction "B_B") (pintype "passive"))
      (node (ref "T49") (pin "3") (pinfunction "C_3") (pintype "passive"))
    )
    (net (code "119") (name "Net-(T50-C)") (class "Default")
      (node (ref "AC7") (pin "B") (pinfunction "B_B") (pintype "passive"))
      (node (ref "T50") (pin "3") (pinfunction "C_3") (pintype "passive"))
    )
    (net (code "120") (name "Net-(T51-C)") (class "Default")
      (node (ref "AC8") (pin "B") (pinfunction "B_B") (pintype "passive"))
      (node (ref "T51") (pin "3") (pinfunction "C_3") (pintype "passive"))
    )
    (net (code "121") (name "Net-(T52-C)") (class "Default")
      (node (ref "AC9") (pin "B") (pinfunction "B_B") (pintype "passive"))
      (node (ref "T52") (pin "3") (pinfunction "C_3") (pintype "passive"))
    )
    (net (code "122") (name "Net-(T53-C)") (class "Default")
      (node (ref "AC10") (pin "B") (pinfunction "B_B") (pintype "passive"))
      (node (ref "T53") (pin "3") (pinfunction "C_3") (pintype "passive"))
    )
    (net (code "123") (name "Net-(T54-C)") (class "Default")
      (node (ref "AC11") (pin "B") (pinfunction "B_B") (pintype "passive"))
      (node (ref "T54") (pin "3") (pinfunction "C_3") (pintype "passive"))
    )
    (net (code "124") (name "Net-(T55-C)") (class "Default")
      (node (ref "MQ0") (pin "B") (pinfunction "B_B") (pintype "passive"))
      (node (ref "T55") (pin "3") (pinfunction "C_3") (pintype "passive"))
    )
    (net (code "125") (name "Net-(T56-C)") (class "Default")
      (node (ref "MQ1") (pin "B") (pinfunction "B_B") (pintype "passive"))
      (node (ref "T56") (pin "3") (pinfunction "C_3") (pintype "passive"))
    )
    (net (code "126") (name "Net-(T57-C)") (class "Default")
      (node (ref "MQ2") (pin "B") (pinfunction "B_B") (pintype "passive"))
      (node (ref "T57") (pin "3") (pinfunction "C_3") (pintype "passive"))
    )
    (net (code "127") (name "Net-(T58-C)") (class "Default")
      (node (ref "MQ3") (pin "B") (pinfunction "B_B") (pintype "passive"))
      (node (ref "T58") (pin "3") (pinfunction "C_3") (pintype "passive"))
    )
    (net (code "128") (name "Net-(T59-C)") (class "Default")
      (node (ref "MQ4") (pin "B") (pinfunction "B_B") (pintype "passive"))
      (node (ref "T59") (pin "3") (pinfunction "C_3") (pintype "passive"))
    )
    (net (code "129") (name "Net-(T60-C)") (class "Default")
      (node (ref "MQ5") (pin "B") (pinfunction "B_B") (pintype "passive"))
      (node (ref "T60") (pin "3") (pinfunction "C_3") (pintype "passive"))
    )
    (net (code "130") (name "Net-(T61-C)") (class "Default")
      (node (ref "MQ6") (pin "B") (pinfunction "B_B") (pintype "passive"))
      (node (ref "T61") (pin "3") (pinfunction "C_3") (pintype "passive"))
    )
    (net (code "131") (name "Net-(T62-C)") (class "Default")
      (node (ref "MQ7") (pin "B") (pinfunction "B_B") (pintype "passive"))
      (node (ref "T62") (pin "3") (pinfunction "C_3") (pintype "passive"))
    )
    (net (code "132") (name "Net-(T63-C)") (class "Default")
      (node (ref "MQ8") (pin "B") (pinfunction "B_B") (pintype "passive"))
      (node (ref "T63") (pin "3") (pinfunction "C_3") (pintype "passive"))
    )
    (net (code "133") (name "Net-(T64-C)") (class "Default")
      (node (ref "MQ9") (pin "B") (pinfunction "B_B") (pintype "passive"))
      (node (ref "T64") (pin "3") (pinfunction "C_3") (pintype "passive"))
    )
    (net (code "134") (name "Net-(T65-C)") (class "Default")
      (node (ref "MQ10") (pin "B") (pinfunction "B_B") (pintype "passive"))
      (node (ref "T65") (pin "3") (pinfunction "C_3") (pintype "passive"))
    )
    (net (code "135") (name "Net-(T66-C)") (class "Default")
      (node (ref "MQ11") (pin "B") (pinfunction "B_B") (pintype "passive"))
      (node (ref "T66") (pin "3") (pinfunction "C_3") (pintype "passive"))
    )
    (net (code "136") (name "Net-(T67-C)") (class "Default")
      (node (ref "SC0") (pin "B") (pinfunction "B_B") (pintype "passive"))
      (node (ref "T67") (pin "3") (pinfunction "C_3") (pintype "passive"))
    )
    (net (code "137") (name "Net-(T68-C)") (class "Default")
      (node (ref "SC1") (pin "B") (pinfunction "B_B") (pintype "passive"))
      (node (ref "T68") (pin "3") (pinfunction "C_3") (pintype "passive"))
    )
    (net (code "138") (name "Net-(T69-C)") (class "Default")
      (node (ref "SC2") (pin "B") (pinfunction "B_B") (pintype "passive"))
      (node (ref "T69") (pin "3") (pinfunction "C_3") (pintype "passive"))
    )
    (net (code "139") (name "Net-(T70-C)") (class "Default")
      (node (ref "SC3") (pin "B") (pinfunction "B_B") (pintype "passive"))
      (node (ref "T70") (pin "3") (pinfunction "C_3") (pintype "passive"))
    )
    (net (code "140") (name "Net-(T71-C)") (class "Default")
      (node (ref "SC4") (pin "B") (pinfunction "B_B") (pintype "passive"))
      (node (ref "T71") (pin "3") (pinfunction "C_3") (pintype "passive"))
    )
    (net (code "141") (name "Net-(T72-C)") (class "Default")
      (node (ref "LINK") (pin "B") (pinfunction "B_B") (pintype "passive"))
      (node (ref "T72") (pin "3") (pinfunction "C_3") (pintype "passive"))
    )
    (net (code "142") (name "Net-(T73-C)") (class "Default")
      (node (ref "ION") (pin "B") (pinfunction "B_B") (pintype "passive"))
      (node (ref "T73") (pin "3") (pinfunction "C_3") (pintype "passive"))
    )
    (net (code "143") (name "Net-(T74-C)") (class "Default")
      (node (ref "PAUSE") (pin "B") (pinfunction "B_B") (pintype "passive"))
      (node (ref "T74") (pin "3") (pinfunction "C_3") (pintype "passive"))
    )
    (net (code "144") (name "Net-(T75-C)") (class "Default")
      (node (ref "RUN") (pin "B") (pinfunction "B_B") (pintype "passive"))
      (node (ref "T75") (pin "3") (pinfunction "C_3") (pintype "passive"))
    )
    (net (code "145") (name "Net-(T76-C)") (class "Default")
      (node (ref "FETCH") (pin "B") (pinfunction "B_B") (pintype "passive"))
      (node (ref "T76") (pin "3") (pinfunction "C_3") (pintype "passive"))
    )
    (net (code "146") (name "Net-(T77-C)") (class "Default")
      (node (ref "EXECUTE") (pin "B") (pinfunction "B_B") (pintype "passive"))
      (node (ref "T77") (pin "3") (pinfunction "C_3") (pintype "passive"))
    )
    (net (code "147") (name "Net-(T78-C)") (class "Default")
      (node (ref "DEFER") (pin "B") (pinfunction "B_B") (pintype "passive"))
      (node (ref "T78") (pin "3") (pinfunction "C_3") (pintype "passive"))
    )
    (net (code "148") (name "Net-(T79-C)") (class "Default")
      (node (ref "T79") (pin "3") (pinfunction "C_3") (pintype "passive"))
      (node (ref "WORDCOUNT") (pin "B") (pinfunction "B_B") (pintype "passive"))
    )
    (net (code "149") (name "Net-(T80-C)") (class "Default")
      (node (ref "CURRENTADDRESS") (pin "B") (pinfunction "B_B") (pintype "passive"))
      (node (ref "T80") (pin "3") (pinfunction "C_3") (pintype "passive"))
    )
    (net (code "150") (name "Net-(T81-C)") (class "Default")
      (node (ref "BREAK") (pin "B") (pinfunction "B_B") (pintype "passive"))
      (node (ref "T81") (pin "3") (pinfunction "C_3") (pintype "passive"))
    )
    (net (code "151") (name "Net-(T82-C)") (class "Default")
      (node (ref "AND") (pin "B") (pinfunction "B_B") (pintype "passive"))
      (node (ref "T82") (pin "3") (pinfunction "C_3") (pintype "passive"))
    )
    (net (code "152") (name "Net-(T83-C)") (class "Default")
      (node (ref "T83") (pin "3") (pinfunction "C_3") (pintype "passive"))
      (node (ref "TAD") (pin "B") (pinfunction "B_B") (pintype "passive"))
    )
    (net (code "153") (name "Net-(T84-C)") (class "Default")
      (node (ref "ISZ") (pin "B") (pinfunction "B_B") (pintype "passive"))
      (node (ref "T84") (pin "3") (pinfunction "C_3") (pintype "passive"))
    )
    (net (code "154") (name "Net-(T85-C)") (class "Default")
      (node (ref "DCA") (pin "B") (pinfunction "B_B") (pintype "passive"))
      (node (ref "T85") (pin "3") (pinfunction "C_3") (pintype "passive"))
    )
    (net (code "155") (name "Net-(T86-C)") (class "Default")
      (node (ref "JMS") (pin "B") (pinfunction "B_B") (pintype "passive"))
      (node (ref "T86") (pin "3") (pinfunction "C_3") (pintype "passive"))
    )
    (net (code "156") (name "Net-(T87-C)") (class "Default")
      (node (ref "JMP") (pin "B") (pinfunction "B_B") (pintype "passive"))
      (node (ref "T87") (pin "3") (pinfunction "C_3") (pintype "passive"))
    )
    (net (code "157") (name "Net-(T88-C)") (class "Default")
      (node (ref "IOT") (pin "B") (pinfunction "B_B") (pintype "passive"))
      (node (ref "T88") (pin "3") (pinfunction "C_3") (pintype "passive"))
    )
    (net (code "158") (name "Net-(T89-C)") (class "Default")
      (node (ref "OPR") (pin "B") (pinfunction "B_B") (pintype "passive"))
      (node (ref "T89") (pin "3") (pinfunction "C_3") (pintype "passive"))
    )
    (net (code "159") (name "OPR") (class "Default")
      (node (ref "D40") (pin "16") (pinfunction "16_16") (pintype "passive"))
      (node (ref "F40BOT") (pin "11") (pinfunction "1_11") (pintype "passive"))
      (node (ref "T89") (pin "2") (pinfunction "B_2") (pintype "passive"))
    )
    (net (code "160") (name "PAUSE") (class "Default")
      (node (ref "D40") (pin "31") (pinfunction "31_31") (pintype "passive"))
      (node (ref "F40TOP") (pin "17") (pinfunction "1_17") (pintype "passive"))
      (node (ref "T74") (pin "2") (pinfunction "B_2") (pintype "passive"))
    )
    (net (code "161") (name "PC0") (class "Default")
      (node (ref "D40TOP") (pin "1") (pinfunction "1_1") (pintype "passive"))
      (node (ref "E40") (pin "1") (pinfunction "1_1") (pintype "passive"))
      (node (ref "T7") (pin "2") (pinfunction "B_2") (pintype "passive"))
    )
    (net (code "162") (name "PC1") (class "Default")
      (node (ref "D40BOT") (pin "5") (pinfunction "1_5") (pintype "passive"))
      (node (ref "E40") (pin "10") (pinfunction "10_10") (pintype "passive"))
      (node (ref "T8") (pin "2") (pinfunction "B_2") (pintype "passive"))
    )
    (net (code "163") (name "PC2") (class "Default")
      (node (ref "D40TOP") (pin "6") (pinfunction "1_6") (pintype "passive"))
      (node (ref "E40") (pin "11") (pinfunction "11_11") (pintype "passive"))
      (node (ref "T9") (pin "2") (pinfunction "B_2") (pintype "passive"))
    )
    (net (code "164") (name "PC3") (class "Default")
      (node (ref "D40BOT") (pin "14") (pinfunction "1_14") (pintype "passive"))
      (node (ref "E40") (pin "24") (pinfunction "24_24") (pintype "passive"))
      (node (ref "T10") (pin "2") (pinfunction "B_2") (pintype "passive"))
    )
    (net (code "165") (name "PC4") (class "Default")
      (node (ref "D40TOP") (pin "14") (pinfunction "1_14") (pintype "passive"))
      (node (ref "E40") (pin "25") (pinfunction "25_25") (pintype "passive"))
      (node (ref "T11") (pin "2") (pinfunction "B_2") (pintype "passive"))
    )
    (net (code "166") (name "PC5") (class "Default")
      (node (ref "D40BOT") (pin "19") (pinfunction "1_19") (pintype "passive"))
      (node (ref "E40") (pin "34") (pinfunction "34_34") (pintype "passive"))
      (node (ref "T12") (pin "2") (pinfunction "B_2") (pintype "passive"))
    )
    (net (code "167") (name "PC6") (class "Default")
      (node (ref "E40TOP") (pin "1") (pinfunction "1_1") (pintype "passive"))
      (node (ref "F40") (pin "1") (pinfunction "1_1") (pintype "passive"))
      (node (ref "T13") (pin "2") (pinfunction "B_2") (pintype "passive"))
    )
    (net (code "168") (name "PC7") (class "Default")
      (node (ref "E40BOT") (pin "5") (pinfunction "1_5") (pintype "passive"))
      (node (ref "F40") (pin "10") (pinfunction "10_10") (pintype "passive"))
      (node (ref "T14") (pin "2") (pinfunction "B_2") (pintype "passive"))
    )
    (net (code "169") (name "PC8") (class "Default")
      (node (ref "E40TOP") (pin "6") (pinfunction "1_6") (pintype "passive"))
      (node (ref "F40") (pin "11") (pinfunction "11_11") (pintype "passive"))
      (node (ref "T15") (pin "2") (pinfunction "B_2") (pintype "passive"))
    )
    (net (code "170") (name "PC9") (class "Default")
      (node (ref "E40BOT") (pin "14") (pinfunction "1_14") (pintype "passive"))
      (node (ref "F40") (pin "24") (pinfunction "24_24") (pintype "passive"))
      (node (ref "T16") (pin "2") (pinfunction "B_2") (pintype "passive"))
    )
    (net (code "171") (name "PC10") (class "Default")
      (node (ref "E40TOP") (pin "14") (pinfunction "1_14") (pintype "passive"))
      (node (ref "F40") (pin "25") (pinfunction "25_25") (pintype "passive"))
      (node (ref "T17") (pin "2") (pinfunction "B_2") (pintype "passive"))
    )
    (net (code "172") (name "PC11") (class "Default")
      (node (ref "E40BOT") (pin "19") (pinfunction "1_19") (pintype "passive"))
      (node (ref "F40") (pin "34") (pinfunction "34_34") (pintype "passive"))
      (node (ref "T18") (pin "2") (pinfunction "B_2") (pintype "passive"))
    )
    (net (code "173") (name "RUN") (class "Default")
      (node (ref "D40") (pin "33") (pinfunction "33_33") (pintype "passive"))
      (node (ref "F40TOP") (pin "18") (pinfunction "1_18") (pintype "passive"))
      (node (ref "T75") (pin "2") (pinfunction "B_2") (pintype "passive"))
    )
    (net (code "174") (name "SC0") (class "Default")
      (node (ref "C40") (pin "9") (pinfunction "9_9") (pintype "passive"))
      (node (ref "C40TOP") (pin "5") (pinfunction "1_5") (pintype "passive"))
      (node (ref "T67") (pin "2") (pinfunction "B_2") (pintype "passive"))
    )
    (net (code "175") (name "SC1") (class "Default")
      (node (ref "C40") (pin "2") (pinfunction "2_2") (pintype "passive"))
      (node (ref "C40BOT") (pin "1") (pinfunction "1_1") (pintype "passive"))
      (node (ref "T68") (pin "2") (pinfunction "B_2") (pintype "passive"))
    )
    (net (code "176") (name "SC2") (class "Default")
      (node (ref "C40") (pin "23") (pinfunction "23_23") (pintype "passive"))
      (node (ref "C40TOP") (pin "13") (pinfunction "1_13") (pintype "passive"))
      (node (ref "T69") (pin "2") (pinfunction "B_2") (pintype "passive"))
    )
    (net (code "177") (name "SC3") (class "Default")
      (node (ref "C40") (pin "12") (pinfunction "12_12") (pintype "passive"))
      (node (ref "C40BOT") (pin "6") (pinfunction "1_6") (pintype "passive"))
      (node (ref "T70") (pin "2") (pinfunction "B_2") (pintype "passive"))
    )
    (net (code "178") (name "SC4") (class "Default")
      (node (ref "C40") (pin "33") (pinfunction "33_33") (pintype "passive"))
      (node (ref "C40TOP") (pin "18") (pinfunction "1_18") (pintype "passive"))
      (node (ref "T71") (pin "2") (pinfunction "B_2") (pintype "passive"))
    )
    (net (code "179") (name "TAD") (class "Default")
      (node (ref "D40") (pin "4") (pinfunction "4_4") (pintype "passive"))
      (node (ref "F40BOT") (pin "2") (pinfunction "1_2") (pintype "passive"))
      (node (ref "T83") (pin "2") (pinfunction "B_2") (pintype "passive"))
    )
    (net (code "180") (name "WC") (class "Default")
      (node (ref "D40") (pin "30") (pinfunction "30_30") (pintype "passive"))
      (node (ref "F40BOT") (pin "17") (pinfunction "1_17") (pintype "passive"))
      (node (ref "T79") (pin "2") (pinfunction "B_2") (pintype "passive"))
    )
    (net (code "181") (name "unconnected-(C40-Pad3)") (class "Default")
      (node (ref "C40") (pin "3") (pinfunction "3_3") (pintype "passive"))
    )
    (net (code "182") (name "unconnected-(C40-Pad4)") (class "Default")
      (node (ref "C40") (pin "4") (pinfunction "4_4") (pintype "passive"))
    )
    (net (code "183") (name "unconnected-(C40-Pad5)") (class "Default")
      (node (ref "C40") (pin "5") (pinfunction "5_5") (pintype "passive"))
    )
    (net (code "184") (name "unconnected-(C40-Pad6)") (class "Default")
      (node (ref "C40") (pin "6") (pinfunction "6_6") (pintype "passive"))
    )
    (net (code "185") (name "unconnected-(C40-Pad7)") (class "Default")
      (node (ref "C40") (pin "7") (pinfunction "7_7") (pintype "passive"))
    )
    (net (code "186") (name "unconnected-(C40-Pad8)") (class "Default")
      (node (ref "C40") (pin "8") (pinfunction "8_8") (pintype "passive"))
    )
    (net (code "187") (name "unconnected-(C40-Pad13)") (class "Default")
      (node (ref "C40") (pin "13") (pinfunction "13_13") (pintype "passive"))
    )
    (net (code "188") (name "unconnected-(C40-Pad14)") (class "Default")
      (node (ref "C40") (pin "14") (pinfunction "14_14") (pintype "passive"))
    )
    (net (code "189") (name "unconnected-(C40-Pad15)") (class "Default")
      (node (ref "C40") (pin "15") (pinfunction "15_15") (pintype "passive"))
    )
    (net (code "190") (name "unconnected-(C40-Pad16)") (class "Default")
      (node (ref "C40") (pin "16") (pinfunction "16_16") (pintype "passive"))
    )
    (net (code "191") (name "unconnected-(C40-Pad21)") (class "Default")
      (node (ref "C40") (pin "21") (pinfunction "21_21") (pintype "passive"))
    )
    (net (code "192") (name "unconnected-(C40-Pad22)") (class "Default")
      (node (ref "C40") (pin "22") (pinfunction "22_22") (pintype "passive"))
    )
    (net (code "193") (name "unconnected-(C40-Pad26)") (class "Default")
      (node (ref "C40") (pin "26") (pinfunction "26_26") (pintype "passive"))
    )
    (net (code "194") (name "unconnected-(C40-Pad27)") (class "Default")
      (node (ref "C40") (pin "27") (pinfunction "27_27") (pintype "passive"))
    )
    (net (code "195") (name "unconnected-(C40-Pad29)") (class "Default")
      (node (ref "C40") (pin "29") (pinfunction "29_29") (pintype "passive"))
    )
    (net (code "196") (name "unconnected-(C40-Pad30)") (class "Default")
      (node (ref "C40") (pin "30") (pinfunction "30_30") (pintype "passive"))
    )
    (net (code "197") (name "unconnected-(C40-Pad31)") (class "Default")
      (node (ref "C40") (pin "31") (pinfunction "31_31") (pintype "passive"))
    )
    (net (code "198") (name "unconnected-(C40-Pad32)") (class "Default")
      (node (ref "C40") (pin "32") (pinfunction "32_32") (pintype "passive"))
    )
    (net (code "199") (name "unconnected-(D40-Pad1)") (class "Default")
      (node (ref "D40") (pin "1") (pinfunction "1_1") (pintype "passive"))
    )
    (net (code "200") (name "unconnected-(D40-Pad3)") (class "Default")
      (node (ref "D40") (pin "3") (pinfunction "3_3") (pintype "passive"))
    )
    (net (code "201") (name "unconnected-(D40-Pad5)") (class "Default")
      (node (ref "D40") (pin "5") (pinfunction "5_5") (pintype "passive"))
    )
    (net (code "202") (name "unconnected-(D40-Pad7)") (class "Default")
      (node (ref "D40") (pin "7") (pinfunction "7_7") (pintype "passive"))
    )
    (net (code "203") (name "unconnected-(D40-Pad9)") (class "Default")
      (node (ref "D40") (pin "9") (pinfunction "9_9") (pintype "passive"))
    )
    (net (code "204") (name "unconnected-(D40-Pad11)") (class "Default")
      (node (ref "D40") (pin "11") (pinfunction "11_11") (pintype "passive"))
    )
    (net (code "205") (name "unconnected-(D40-Pad13)") (class "Default")
      (node (ref "D40") (pin "13") (pinfunction "13_13") (pintype "passive"))
    )
    (net (code "206") (name "unconnected-(D40-Pad14)") (class "Default")
      (node (ref "D40") (pin "14") (pinfunction "14_14") (pintype "passive"))
    )
    (net (code "207") (name "unconnected-(D40-Pad15)") (class "Default")
      (node (ref "D40") (pin "15") (pinfunction "15_15") (pintype "passive"))
    )
    (net (code "208") (name "unconnected-(D40-Pad21)") (class "Default")
      (node (ref "D40") (pin "21") (pinfunction "21_21") (pintype "passive"))
    )
    (net (code "209") (name "unconnected-(D40-Pad25)") (class "Default")
      (node (ref "D40") (pin "25") (pinfunction "25_25") (pintype "passive"))
    )
    (net (code "210") (name "unconnected-(D40-Pad27)") (class "Default")
      (node (ref "D40") (pin "27") (pinfunction "27_27") (pintype "passive"))
    )
    (net (code "211") (name "unconnected-(D40-Pad29)") (class "Default")
      (node (ref "D40") (pin "29") (pinfunction "29_29") (pintype "passive"))
    )
  )
)
